# UPCNSL-ABS-FLS-POL_test-v1_0.net
KiCad netlist of a schematic drawn in Altium Designer
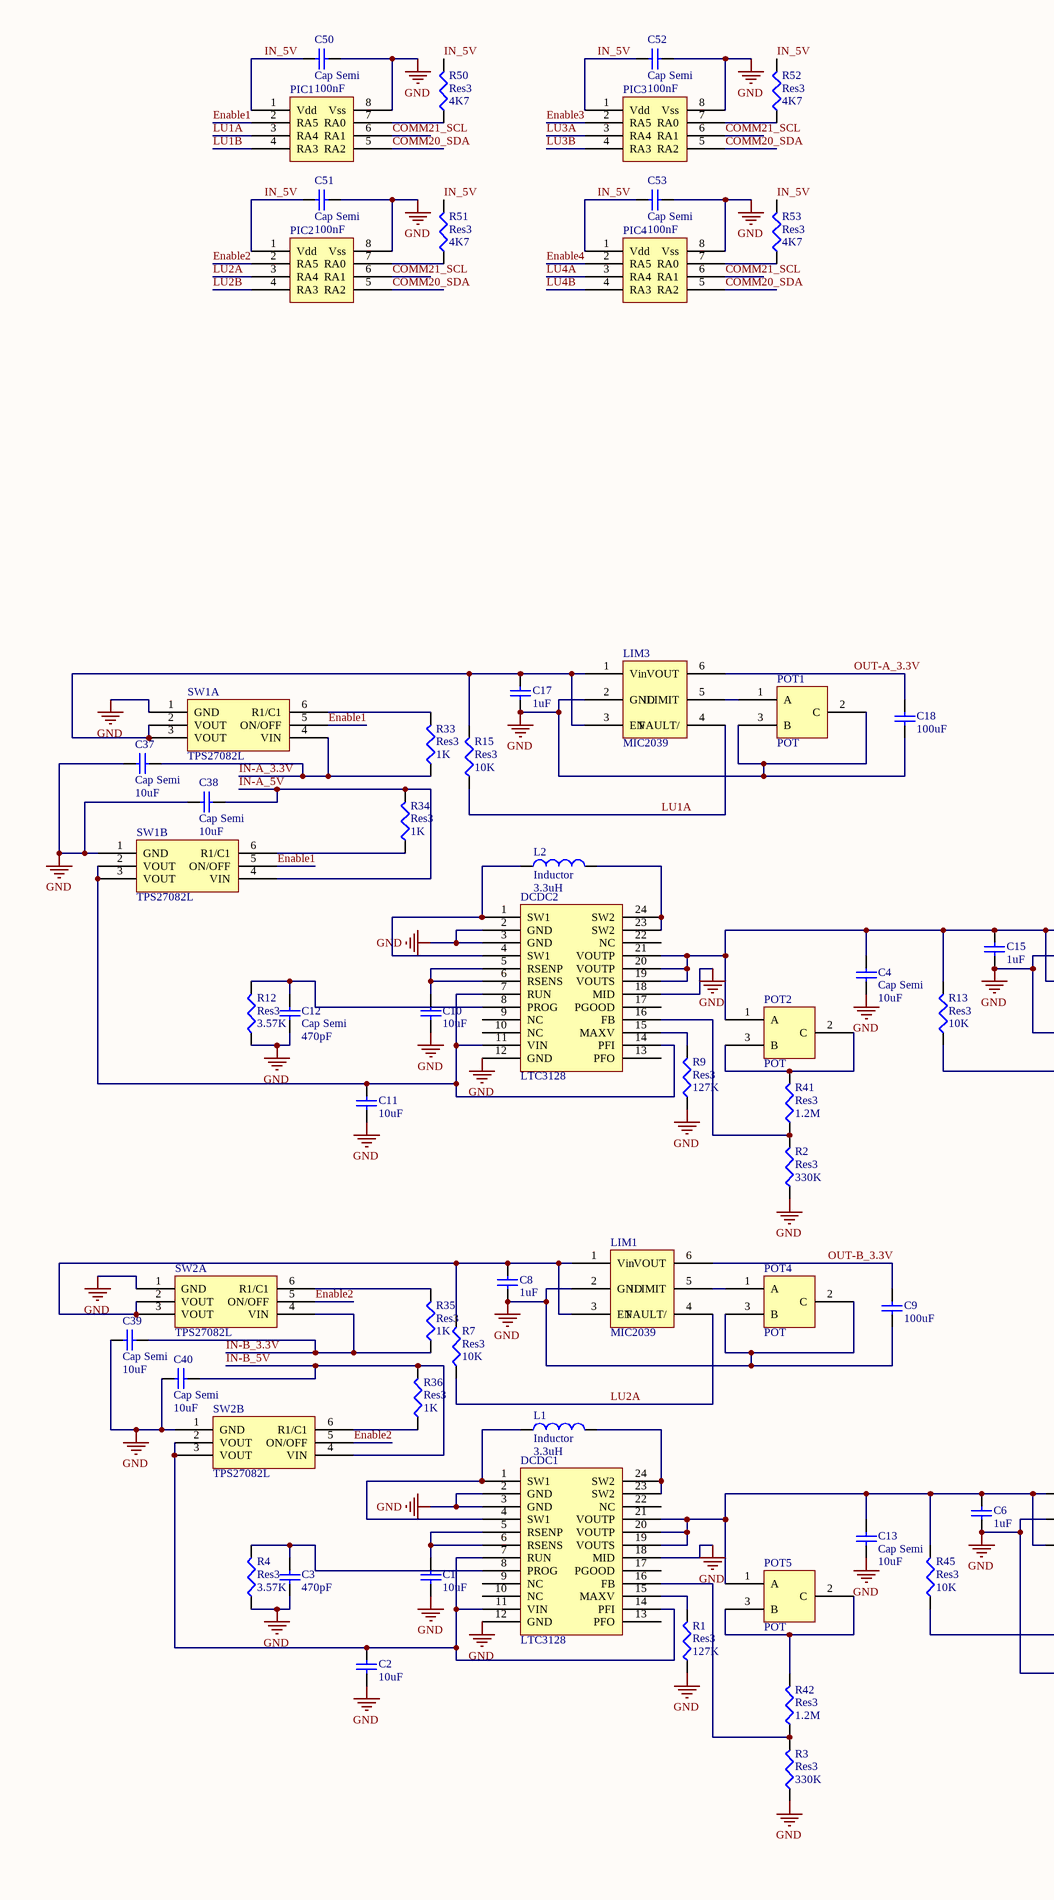
[diagram p0: UPCNSL-ABS-FLS-POL_test-v1.0.SchDoc, left]
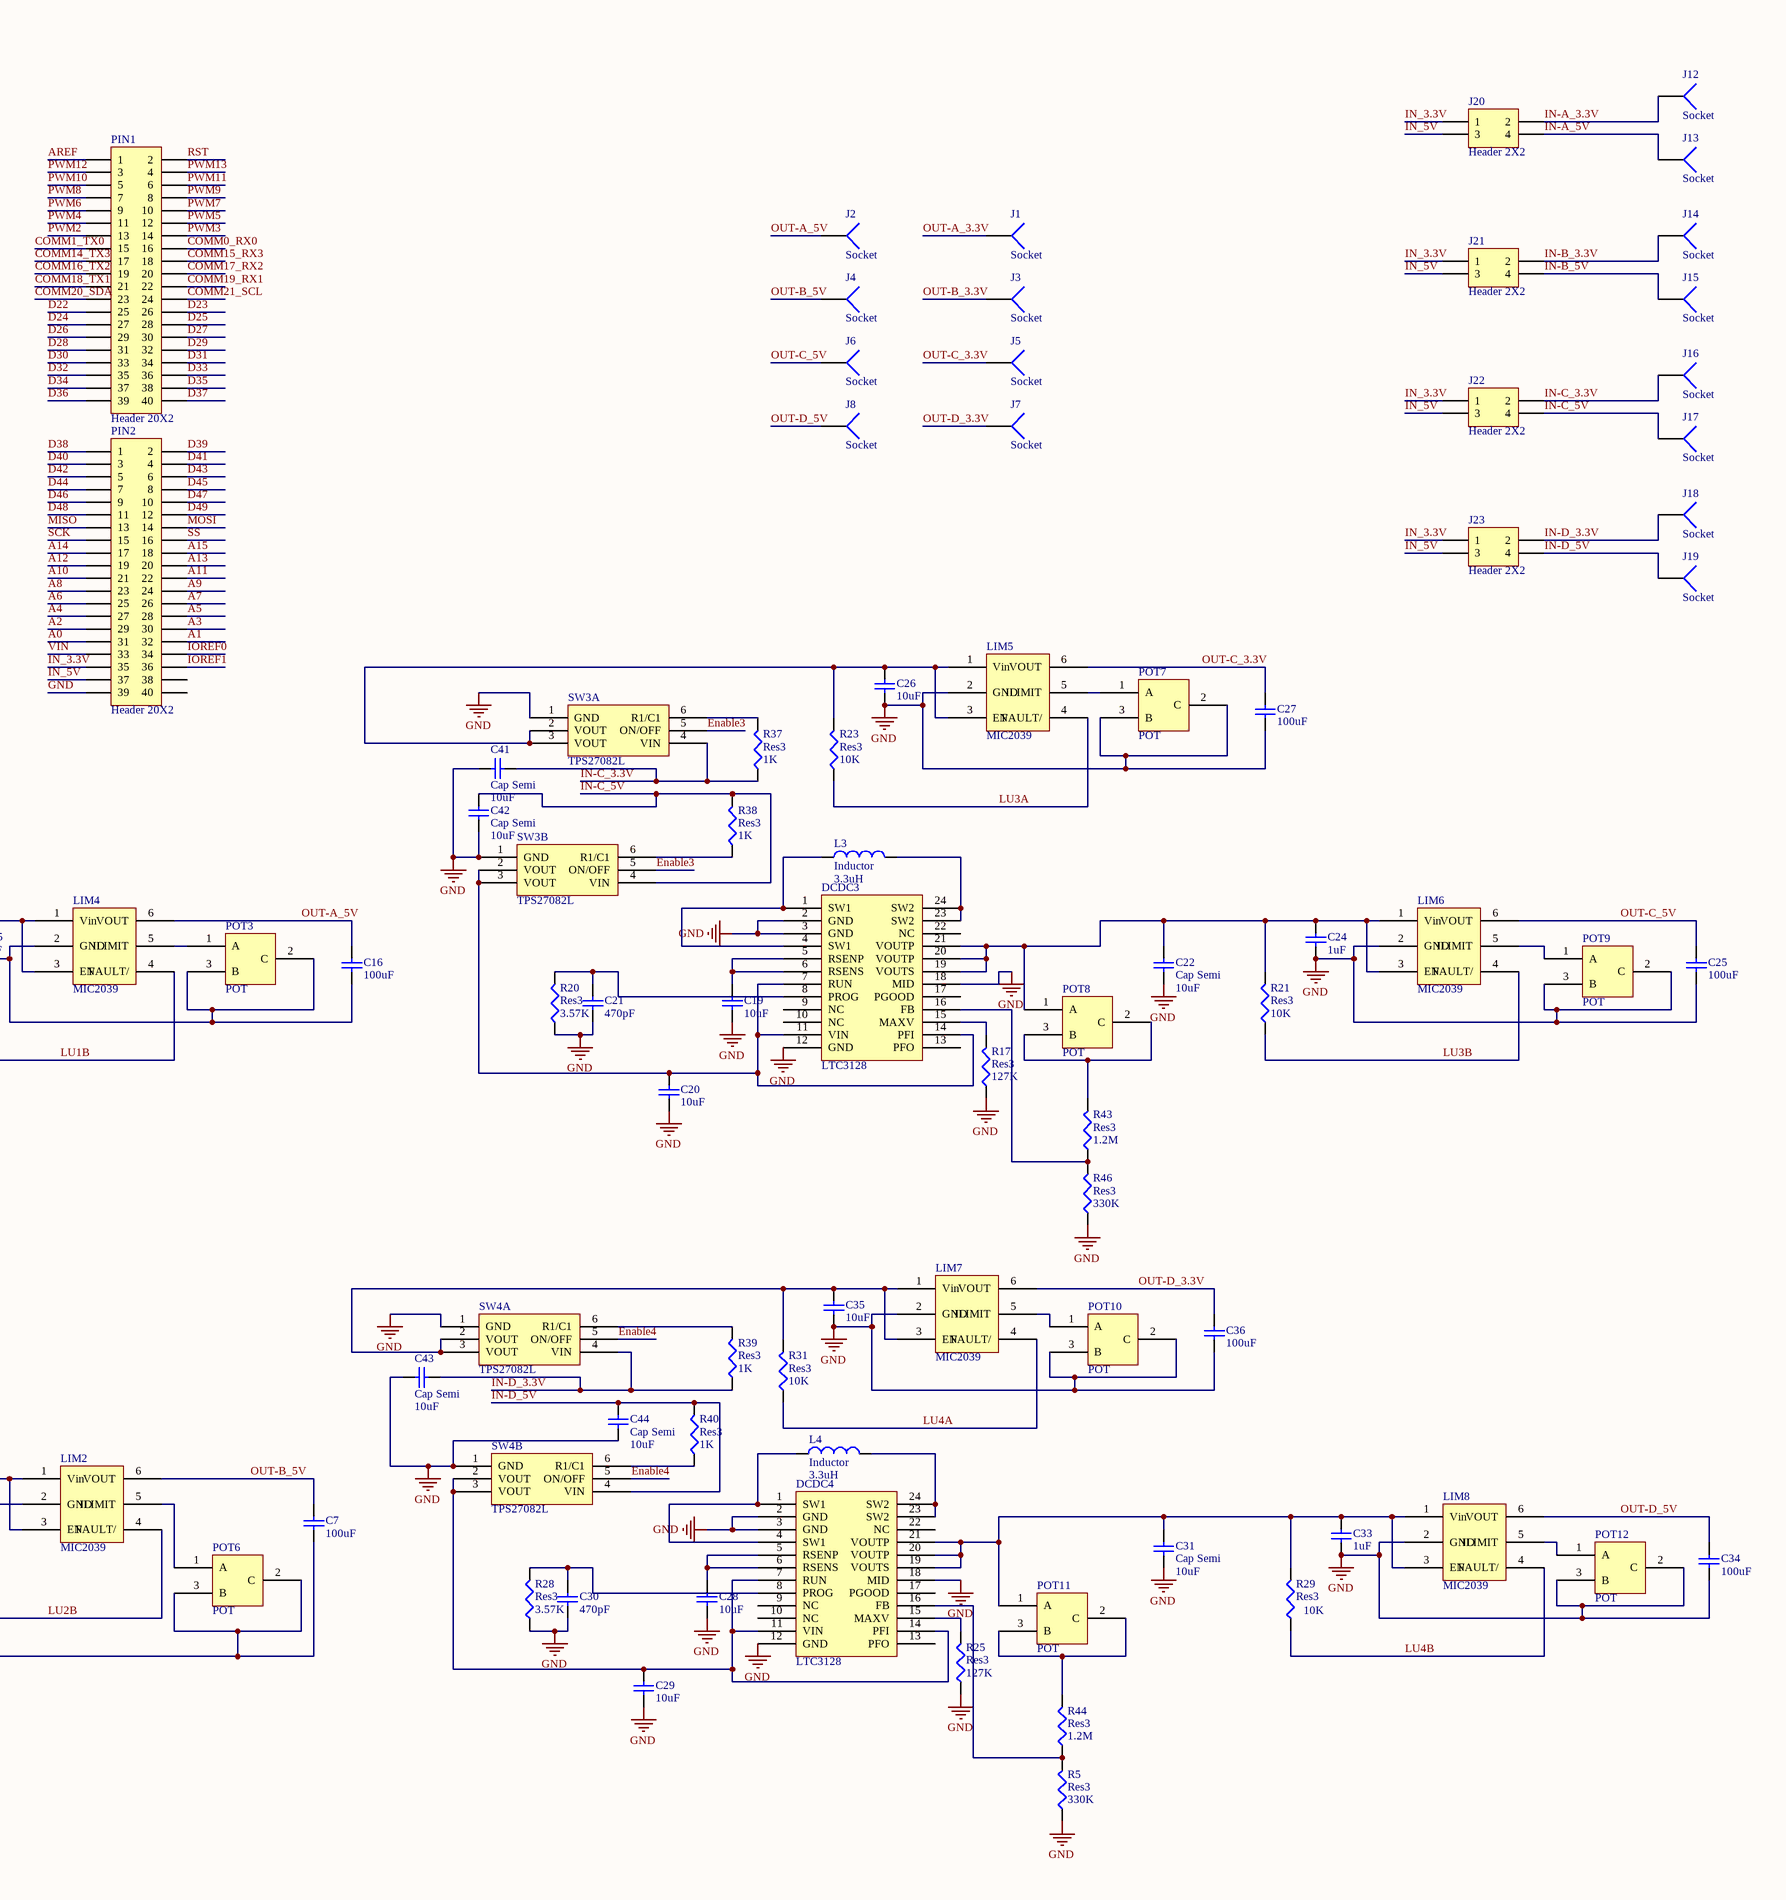
[diagram p1: UPCNSL-ABS-FLS-POL_test-v1.0.SchDoc, right]

(export (version "E")
  (design (tool "Eeschema 10.0.6"))
  (components
    (comp (ref "C1")
      (value "10uF")
      (footprint "CAP0603")
      (description "Capacitor")
      (fields (field (name "Comment") "CAP0603"))
      (libsource (lib "EPS") (part "CAP0603"))
    )
    (comp (ref "C2")
      (value "10uF")
      (footprint "CAP0603")
      (description "Capacitor")
      (fields (field (name "Comment") "CAP0603"))
      (libsource (lib "EPS") (part "CAP0603"))
    )
    (comp (ref "C3")
      (value "470pF")
      (footprint "CAP0603")
      (description "Capacitor")
      (fields (field (name "Comment") "CAP0603"))
      (libsource (lib "EPS") (part "CAP0603"))
    )
    (comp (ref "C4")
      (value "Cap Semi")
      (footprint "1608[0603]")
      (description "Capacitor (Semiconductor SIM Model)")
      (fields (field (name "ALTIUM_VALUE") "10uF") (field (name "PUBLISHER") "Altium Limited"))
      (libsource (lib "Miscellaneous Devices") (part "Cap Semi"))
    )
    (comp (ref "C6")
      (value "1uF")
      (footprint "CAP0603")
      (description "Capacitor")
      (fields (field (name "Comment") "CAP0603"))
      (libsource (lib "EPS") (part "CAP0603"))
    )
    (comp (ref "C7")
      (value "100uF")
      (footprint "CAP0603")
      (description "Capacitor")
      (fields (field (name "Comment") "CAP0603"))
      (libsource (lib "EPS") (part "CAP0603"))
    )
    (comp (ref "C8")
      (value "1uF")
      (footprint "CAP0603")
      (description "Capacitor")
      (fields (field (name "Comment") "CAP0603"))
      (libsource (lib "EPS") (part "CAP0603"))
    )
    (comp (ref "C9")
      (value "100uF")
      (footprint "CAP0603")
      (description "Capacitor")
      (fields (field (name "Comment") "CAP0603"))
      (libsource (lib "EPS") (part "CAP0603"))
    )
    (comp (ref "C10")
      (value "10uF")
      (footprint "CAP0603")
      (description "Capacitor")
      (fields (field (name "Comment") "CAP0603"))
      (libsource (lib "EPS") (part "CAP0603"))
    )
    (comp (ref "C11")
      (value "10uF")
      (footprint "CAP0603")
      (description "Capacitor")
      (fields (field (name "Comment") "CAP0603"))
      (libsource (lib "EPS") (part "CAP0603"))
    )
    (comp (ref "C12")
      (value "Cap Semi")
      (footprint "1608[0603]")
      (description "Capacitor (Semiconductor SIM Model)")
      (fields (field (name "ALTIUM_VALUE") "470pF") (field (name "PUBLISHER") "Altium Limited"))
      (libsource (lib "Miscellaneous Devices") (part "Cap Semi"))
    )
    (comp (ref "C13")
      (value "Cap Semi")
      (footprint "1608[0603]")
      (description "Capacitor (Semiconductor SIM Model)")
      (fields (field (name "ALTIUM_VALUE") "10uF") (field (name "PUBLISHER") "Altium Limited"))
      (libsource (lib "Miscellaneous Devices") (part "Cap Semi"))
    )
    (comp (ref "C15")
      (value "1uF")
      (footprint "CAP0603")
      (description "Capacitor")
      (fields (field (name "Comment") "CAP0603"))
      (libsource (lib "EPS") (part "CAP0603"))
    )
    (comp (ref "C16")
      (value "100uF")
      (footprint "CAP0603")
      (description "Capacitor")
      (fields (field (name "Comment") "CAP0603"))
      (libsource (lib "EPS") (part "CAP0603"))
    )
    (comp (ref "C17")
      (value "1uF")
      (footprint "CAP0603")
      (description "Capacitor")
      (fields (field (name "Comment") "CAP0603"))
      (libsource (lib "EPS") (part "CAP0603"))
    )
    (comp (ref "C18")
      (value "100uF")
      (footprint "CAP0603")
      (description "Capacitor")
      (fields (field (name "Comment") "CAP0603"))
      (libsource (lib "EPS") (part "CAP0603"))
    )
    (comp (ref "C19")
      (value "10uF")
      (footprint "CAP0603")
      (description "Capacitor")
      (fields (field (name "Comment") "CAP0603"))
      (libsource (lib "EPS") (part "CAP0603"))
    )
    (comp (ref "C20")
      (value "10uF")
      (footprint "CAP0603")
      (description "Capacitor")
      (fields (field (name "Comment") "CAP0603"))
      (libsource (lib "EPS") (part "CAP0603"))
    )
    (comp (ref "C21")
      (value "470pF")
      (footprint "CAP0603")
      (description "Capacitor")
      (fields (field (name "Comment") "CAP0603"))
      (libsource (lib "EPS") (part "CAP0603"))
    )
    (comp (ref "C22")
      (value "Cap Semi")
      (footprint "1608[0603]")
      (description "Capacitor (Semiconductor SIM Model)")
      (fields (field (name "ALTIUM_VALUE") "10uF") (field (name "PUBLISHER") "Altium Limited"))
      (libsource (lib "Miscellaneous Devices") (part "Cap Semi"))
    )
    (comp (ref "C24")
      (value "1uF")
      (footprint "CAP0603")
      (description "Capacitor")
      (fields (field (name "Comment") "CAP0603"))
      (libsource (lib "EPS") (part "CAP0603"))
    )
    (comp (ref "C25")
      (value "100uF")
      (footprint "CAP0603")
      (description "Capacitor")
      (fields (field (name "Comment") "CAP0603"))
      (libsource (lib "EPS") (part "CAP0603"))
    )
    (comp (ref "C26")
      (value "10uF")
      (footprint "CAP0603")
      (description "Capacitor")
      (fields (field (name "Comment") "CAP0603"))
      (libsource (lib "EPS") (part "CAP0603"))
    )
    (comp (ref "C27")
      (value "100uF")
      (footprint "CAP0603")
      (description "Capacitor")
      (fields (field (name "Comment") "CAP0603"))
      (libsource (lib "EPS") (part "CAP0603"))
    )
    (comp (ref "C28")
      (value "10uF")
      (footprint "CAP0603")
      (description "Capacitor")
      (fields (field (name "Comment") "CAP0603"))
      (libsource (lib "EPS") (part "CAP0603"))
    )
    (comp (ref "C29")
      (value "10uF")
      (footprint "CAP0603")
      (description "Capacitor")
      (fields (field (name "Comment") "CAP0603"))
      (libsource (lib "EPS") (part "CAP0603"))
    )
    (comp (ref "C30")
      (value "470pF")
      (footprint "CAP0603")
      (description "Capacitor")
      (fields (field (name "Comment") "CAP0603"))
      (libsource (lib "EPS") (part "CAP0603"))
    )
    (comp (ref "C31")
      (value "Cap Semi")
      (footprint "1608[0603]")
      (description "Capacitor (Semiconductor SIM Model)")
      (fields (field (name "ALTIUM_VALUE") "10uF") (field (name "PUBLISHER") "Altium Limited"))
      (libsource (lib "Miscellaneous Devices") (part "Cap Semi"))
    )
    (comp (ref "C33")
      (value "1uF")
      (footprint "CAP0603")
      (description "Capacitor")
      (fields (field (name "Comment") "CAP0603"))
      (libsource (lib "EPS") (part "CAP0603"))
    )
    (comp (ref "C34")
      (value "100uF")
      (footprint "CAP0603")
      (description "Capacitor")
      (fields (field (name "Comment") "CAP0603"))
      (libsource (lib "EPS") (part "CAP0603"))
    )
    (comp (ref "C35")
      (value "10uF")
      (footprint "CAP0603")
      (description "Capacitor")
      (fields (field (name "Comment") "CAP0603"))
      (libsource (lib "EPS") (part "CAP0603"))
    )
    (comp (ref "C36")
      (value "100uF")
      (footprint "CAP0603")
      (description "Capacitor")
      (fields (field (name "Comment") "CAP0603"))
      (libsource (lib "EPS") (part "CAP0603"))
    )
    (comp (ref "C37")
      (value "Cap Semi")
      (footprint "1608[0603]")
      (description "Capacitor (Semiconductor SIM Model)")
      (fields (field (name "ALTIUM_VALUE") "10uF") (field (name "PUBLISHER") "Altium Limited"))
      (libsource (lib "Miscellaneous Devices") (part "Cap Semi"))
    )
    (comp (ref "C38")
      (value "Cap Semi")
      (footprint "1608[0603]")
      (description "Capacitor (Semiconductor SIM Model)")
      (fields (field (name "ALTIUM_VALUE") "10uF") (field (name "PUBLISHER") "Altium Limited"))
      (libsource (lib "Miscellaneous Devices") (part "Cap Semi"))
    )
    (comp (ref "C39")
      (value "Cap Semi")
      (footprint "1608[0603]")
      (description "Capacitor (Semiconductor SIM Model)")
      (fields (field (name "ALTIUM_VALUE") "10uF") (field (name "PUBLISHER") "Altium Limited"))
      (libsource (lib "Miscellaneous Devices") (part "Cap Semi"))
    )
    (comp (ref "C40")
      (value "Cap Semi")
      (footprint "1608[0603]")
      (description "Capacitor (Semiconductor SIM Model)")
      (fields (field (name "ALTIUM_VALUE") "10uF") (field (name "PUBLISHER") "Altium Limited"))
      (libsource (lib "Miscellaneous Devices") (part "Cap Semi"))
    )
    (comp (ref "C41")
      (value "Cap Semi")
      (footprint "1608[0603]")
      (description "Capacitor (Semiconductor SIM Model)")
      (fields (field (name "ALTIUM_VALUE") "10uF") (field (name "PUBLISHER") "Altium Limited"))
      (libsource (lib "Miscellaneous Devices") (part "Cap Semi"))
    )
    (comp (ref "C42")
      (value "Cap Semi")
      (footprint "1608[0603]")
      (description "Capacitor (Semiconductor SIM Model)")
      (fields (field (name "ALTIUM_VALUE") "10uF") (field (name "PUBLISHER") "Altium Limited"))
      (libsource (lib "Miscellaneous Devices") (part "Cap Semi"))
    )
    (comp (ref "C43")
      (value "Cap Semi")
      (footprint "1608[0603]")
      (description "Capacitor (Semiconductor SIM Model)")
      (fields (field (name "ALTIUM_VALUE") "10uF") (field (name "PUBLISHER") "Altium Limited"))
      (libsource (lib "Miscellaneous Devices") (part "Cap Semi"))
    )
    (comp (ref "C44")
      (value "Cap Semi")
      (footprint "1608[0603]")
      (description "Capacitor (Semiconductor SIM Model)")
      (fields (field (name "ALTIUM_VALUE") "10uF") (field (name "PUBLISHER") "Altium Limited"))
      (libsource (lib "Miscellaneous Devices") (part "Cap Semi"))
    )
    (comp (ref "C50")
      (value "Cap Semi")
      (footprint "1608[0603]")
      (description "Capacitor (Semiconductor SIM Model)")
      (fields (field (name "ALTIUM_VALUE") "100nF") (field (name "PUBLISHER") "Altium Limited"))
      (libsource (lib "Miscellaneous Devices") (part "Cap Semi"))
    )
    (comp (ref "C51")
      (value "Cap Semi")
      (footprint "1608[0603]")
      (description "Capacitor (Semiconductor SIM Model)")
      (fields (field (name "ALTIUM_VALUE") "100nF") (field (name "PUBLISHER") "Altium Limited"))
      (libsource (lib "Miscellaneous Devices") (part "Cap Semi"))
    )
    (comp (ref "C52")
      (value "Cap Semi")
      (footprint "1608[0603]")
      (description "Capacitor (Semiconductor SIM Model)")
      (fields (field (name "ALTIUM_VALUE") "100nF") (field (name "PUBLISHER") "Altium Limited"))
      (libsource (lib "Miscellaneous Devices") (part "Cap Semi"))
    )
    (comp (ref "C53")
      (value "Cap Semi")
      (footprint "1608[0603]")
      (description "Capacitor (Semiconductor SIM Model)")
      (fields (field (name "ALTIUM_VALUE") "100nF") (field (name "PUBLISHER") "Altium Limited"))
      (libsource (lib "Miscellaneous Devices") (part "Cap Semi"))
    )
    (comp (ref "DCDC1")
      (value "LTC3128")
      (footprint "SOP-24")
      (libsource (lib "FLATSAT_PHONE_DCDC2") (part "Component_1"))
    )
    (comp (ref "DCDC2")
      (value "LTC3128")
      (footprint "SOP-24")
      (libsource (lib "FLATSAT_PHONE_DCDC2") (part "Component_1"))
    )
    (comp (ref "DCDC3")
      (value "LTC3128")
      (footprint "SOP-24")
      (libsource (lib "FLATSAT_PHONE_DCDC2") (part "Component_1"))
    )
    (comp (ref "DCDC4")
      (value "LTC3128")
      (footprint "SOP-24")
      (libsource (lib "FLATSAT_PHONE_DCDC2") (part "Component_1"))
    )
    (comp (ref "J1")
      (value "Socket")
      (footprint "PIN1")
      (fields (field (name "PUBLISHER") "Altium Limited"))
      (libsource (lib "Miscellaneous Connectors") (part "Socket"))
    )
    (comp (ref "J2")
      (value "Socket")
      (footprint "PIN1")
      (fields (field (name "PUBLISHER") "Altium Limited"))
      (libsource (lib "Miscellaneous Connectors") (part "Socket"))
    )
    (comp (ref "J3")
      (value "Socket")
      (footprint "PIN1")
      (fields (field (name "PUBLISHER") "Altium Limited"))
      (libsource (lib "Miscellaneous Connectors") (part "Socket"))
    )
    (comp (ref "J4")
      (value "Socket")
      (footprint "PIN1")
      (fields (field (name "PUBLISHER") "Altium Limited"))
      (libsource (lib "Miscellaneous Connectors") (part "Socket"))
    )
    (comp (ref "J5")
      (value "Socket")
      (footprint "PIN1")
      (fields (field (name "PUBLISHER") "Altium Limited"))
      (libsource (lib "Miscellaneous Connectors") (part "Socket"))
    )
    (comp (ref "J6")
      (value "Socket")
      (footprint "PIN1")
      (fields (field (name "PUBLISHER") "Altium Limited"))
      (libsource (lib "Miscellaneous Connectors") (part "Socket"))
    )
    (comp (ref "J7")
      (value "Socket")
      (footprint "PIN1")
      (fields (field (name "PUBLISHER") "Altium Limited"))
      (libsource (lib "Miscellaneous Connectors") (part "Socket"))
    )
    (comp (ref "J8")
      (value "Socket")
      (footprint "PIN1")
      (fields (field (name "PUBLISHER") "Altium Limited"))
      (libsource (lib "Miscellaneous Connectors") (part "Socket"))
    )
    (comp (ref "J12")
      (value "Socket")
      (footprint "PIN1")
      (fields (field (name "PUBLISHER") "Altium Limited"))
      (libsource (lib "Miscellaneous Connectors") (part "Socket"))
    )
    (comp (ref "J13")
      (value "Socket")
      (footprint "PIN1")
      (fields (field (name "PUBLISHER") "Altium Limited"))
      (libsource (lib "Miscellaneous Connectors") (part "Socket"))
    )
    (comp (ref "J14")
      (value "Socket")
      (footprint "PIN1")
      (fields (field (name "PUBLISHER") "Altium Limited"))
      (libsource (lib "Miscellaneous Connectors") (part "Socket"))
    )
    (comp (ref "J15")
      (value "Socket")
      (footprint "PIN1")
      (fields (field (name "PUBLISHER") "Altium Limited"))
      (libsource (lib "Miscellaneous Connectors") (part "Socket"))
    )
    (comp (ref "J16")
      (value "Socket")
      (footprint "PIN1")
      (fields (field (name "PUBLISHER") "Altium Limited"))
      (libsource (lib "Miscellaneous Connectors") (part "Socket"))
    )
    (comp (ref "J17")
      (value "Socket")
      (footprint "PIN1")
      (fields (field (name "PUBLISHER") "Altium Limited"))
      (libsource (lib "Miscellaneous Connectors") (part "Socket"))
    )
    (comp (ref "J18")
      (value "Socket")
      (footprint "PIN1")
      (fields (field (name "PUBLISHER") "Altium Limited"))
      (libsource (lib "Miscellaneous Connectors") (part "Socket"))
    )
    (comp (ref "J19")
      (value "Socket")
      (footprint "PIN1")
      (fields (field (name "PUBLISHER") "Altium Limited"))
      (libsource (lib "Miscellaneous Connectors") (part "Socket"))
    )
    (comp (ref "J20")
      (value "Header 2X2")
      (footprint "HDR2X2")
      (description "Header, 2-Pin, Dual row")
      (fields (field (name "PUBLISHER") "Altium Limited"))
      (libsource (lib "Miscellaneous Connectors") (part "Header 2X2"))
    )
    (comp (ref "J21")
      (value "Header 2X2")
      (footprint "HDR2X2")
      (description "Header, 2-Pin, Dual row")
      (fields (field (name "PUBLISHER") "Altium Limited"))
      (libsource (lib "Miscellaneous Connectors") (part "Header 2X2"))
    )
    (comp (ref "J22")
      (value "Header 2X2")
      (footprint "HDR2X2")
      (description "Header, 2-Pin, Dual row")
      (fields (field (name "PUBLISHER") "Altium Limited"))
      (libsource (lib "Miscellaneous Connectors") (part "Header 2X2"))
    )
    (comp (ref "J23")
      (value "Header 2X2")
      (footprint "HDR2X2")
      (description "Header, 2-Pin, Dual row")
      (fields (field (name "PUBLISHER") "Altium Limited"))
      (libsource (lib "Miscellaneous Connectors") (part "Header 2X2"))
    )
    (comp (ref "L1")
      (value "Inductor")
      (footprint "MPLC0703R3")
      (fields (field (name "ALTIUM_VALUE") "3.3uH") (field (name "PUBLISHER") "Altium Limited"))
      (libsource (lib "Miscellaneous Devices") (part "Inductor"))
    )
    (comp (ref "L2")
      (value "Inductor")
      (footprint "MPLC0703R3")
      (fields (field (name "ALTIUM_VALUE") "3.3uH") (field (name "PUBLISHER") "Altium Limited"))
      (libsource (lib "Miscellaneous Devices") (part "Inductor"))
    )
    (comp (ref "L3")
      (value "Inductor")
      (footprint "MPLC0703R3")
      (fields (field (name "ALTIUM_VALUE") "3.3uH") (field (name "PUBLISHER") "Altium Limited"))
      (libsource (lib "Miscellaneous Devices") (part "Inductor"))
    )
    (comp (ref "L4")
      (value "Inductor")
      (footprint "MPLC0703R3")
      (fields (field (name "ALTIUM_VALUE") "3.3uH") (field (name "PUBLISHER") "Altium Limited"))
      (libsource (lib "Miscellaneous Devices") (part "Inductor"))
    )
    (comp (ref "LIM1")
      (value "MIC2039")
      (footprint "SOT23-6_M")
      (libsource (lib "FLATSAT_PHONE") (part "MIC2039"))
    )
    (comp (ref "LIM2")
      (value "MIC2039")
      (footprint "SOT23-6_M")
      (libsource (lib "FLATSAT_PHONE") (part "MIC2039"))
    )
    (comp (ref "LIM3")
      (value "MIC2039")
      (footprint "SOT23-6_M")
      (libsource (lib "FLATSAT_PHONE") (part "MIC2039"))
    )
    (comp (ref "LIM4")
      (value "MIC2039")
      (footprint "SOT23-6_M")
      (libsource (lib "FLATSAT_PHONE") (part "MIC2039"))
    )
    (comp (ref "LIM5")
      (value "MIC2039")
      (footprint "SOT23-6_M")
      (libsource (lib "FLATSAT_PHONE") (part "MIC2039"))
    )
    (comp (ref "LIM6")
      (value "MIC2039")
      (footprint "SOT23-6_M")
      (libsource (lib "FLATSAT_PHONE") (part "MIC2039"))
    )
    (comp (ref "LIM7")
      (value "MIC2039")
      (footprint "SOT23-6_M")
      (libsource (lib "FLATSAT_PHONE") (part "MIC2039"))
    )
    (comp (ref "LIM8")
      (value "MIC2039")
      (footprint "SOT23-6_M")
      (libsource (lib "FLATSAT_PHONE") (part "MIC2039"))
    )
    (comp (ref "PIC1")
      (value "SOCOL-8P")
      (footprint "SOCOL-8P")
      (libsource (lib "SOCOL-8P") (part "SOCOL-8P"))
    )
    (comp (ref "PIC2")
      (value "SOCOL-8P")
      (footprint "SOCOL-8P")
      (libsource (lib "SOCOL-8P") (part "SOCOL-8P"))
    )
    (comp (ref "PIC3")
      (value "SOCOL-8P")
      (footprint "SOCOL-8P")
      (libsource (lib "SOCOL-8P") (part "SOCOL-8P"))
    )
    (comp (ref "PIC4")
      (value "SOCOL-8P")
      (footprint "SOCOL-8P")
      (libsource (lib "SOCOL-8P") (part "SOCOL-8P"))
    )
    (comp (ref "PIN1")
      (value "Header 20X2")
      (footprint "HDR2X20")
      (description "Header, 20-Pin, Dual row")
      (fields (field (name "PUBLISHER") "Altium Limited"))
      (libsource (lib "Miscellaneous Connectors") (part "Header 20X2"))
    )
    (comp (ref "PIN2")
      (value "Header 20X2")
      (footprint "HDR2X20")
      (description "Header, 20-Pin, Dual row")
      (fields (field (name "PUBLISHER") "Altium Limited"))
      (libsource (lib "Miscellaneous Connectors") (part "Header 20X2"))
    )
    (comp (ref "POT1")
      (value "POT")
      (footprint "POT")
      (libsource (lib "FLATSAT_PHONE_POT") (part "component_1"))
    )
    (comp (ref "POT2")
      (value "POT")
      (footprint "POT2")
      (libsource (lib "FLATSAT_PHONE_POT") (part "component_1"))
    )
    (comp (ref "POT3")
      (value "POT")
      (footprint "POT")
      (libsource (lib "FLATSAT_PHONE_POT") (part "component_1"))
    )
    (comp (ref "POT4")
      (value "POT")
      (footprint "POT")
      (libsource (lib "FLATSAT_PHONE_POT") (part "component_1"))
    )
    (comp (ref "POT5")
      (value "POT")
      (footprint "POT2")
      (libsource (lib "FLATSAT_PHONE_POT") (part "component_1"))
    )
    (comp (ref "POT6")
      (value "POT")
      (footprint "POT")
      (libsource (lib "FLATSAT_PHONE_POT") (part "component_1"))
    )
    (comp (ref "POT7")
      (value "POT")
      (footprint "POT")
      (libsource (lib "FLATSAT_PHONE_POT") (part "component_1"))
    )
    (comp (ref "POT8")
      (value "POT")
      (footprint "POT2")
      (libsource (lib "FLATSAT_PHONE_POT") (part "component_1"))
    )
    (comp (ref "POT9")
      (value "POT")
      (footprint "POT")
      (libsource (lib "FLATSAT_PHONE_POT") (part "component_1"))
    )
    (comp (ref "POT10")
      (value "POT")
      (footprint "POT")
      (libsource (lib "FLATSAT_PHONE_POT") (part "component_1"))
    )
    (comp (ref "POT11")
      (value "POT")
      (footprint "POT2")
      (libsource (lib "FLATSAT_PHONE_POT") (part "component_1"))
    )
    (comp (ref "POT12")
      (value "POT")
      (footprint "POT")
      (libsource (lib "FLATSAT_PHONE_POT") (part "component_1"))
    )
    (comp (ref "R1")
      (value "Res3")
      (footprint "J1-0603")
      (description "Resistor")
      (fields (field (name "ALTIUM_VALUE") "127K") (field (name "PUBLISHER") "Altium Limited"))
      (libsource (lib "Miscellaneous Devices") (part "Res3"))
    )
    (comp (ref "R2")
      (value "Res3")
      (footprint "J1-0603")
      (description "Resistor")
      (fields (field (name "ALTIUM_VALUE") "330K") (field (name "PUBLISHER") "Altium Limited"))
      (libsource (lib "Miscellaneous Devices") (part "Res3"))
    )
    (comp (ref "R3")
      (value "Res3")
      (footprint "J1-0603")
      (description "Resistor")
      (fields (field (name "ALTIUM_VALUE") "330K") (field (name "PUBLISHER") "Altium Limited"))
      (libsource (lib "Miscellaneous Devices") (part "Res3"))
    )
    (comp (ref "R4")
      (value "Res3")
      (footprint "J1-0603")
      (description "Resistor")
      (fields (field (name "ALTIUM_VALUE") "3.57K") (field (name "PUBLISHER") "Altium Limited"))
      (libsource (lib "Miscellaneous Devices") (part "Res3"))
    )
    (comp (ref "R5")
      (value "Res3")
      (footprint "J1-0603")
      (description "Resistor")
      (fields (field (name "ALTIUM_VALUE") "330K") (field (name "PUBLISHER") "Altium Limited"))
      (libsource (lib "Miscellaneous Devices") (part "Res3"))
    )
    (comp (ref "R7")
      (value "Res3")
      (footprint "J1-0603")
      (description "Resistor")
      (fields (field (name "ALTIUM_VALUE") "10K") (field (name "PUBLISHER") "Altium Limited"))
      (libsource (lib "Miscellaneous Devices") (part "Res3"))
    )
    (comp (ref "R9")
      (value "Res3")
      (footprint "J1-0603")
      (description "Resistor")
      (fields (field (name "ALTIUM_VALUE") "127K") (field (name "PUBLISHER") "Altium Limited"))
      (libsource (lib "Miscellaneous Devices") (part "Res3"))
    )
    (comp (ref "R12")
      (value "Res3")
      (footprint "J1-0603")
      (description "Resistor")
      (fields (field (name "ALTIUM_VALUE") "3.57K") (field (name "PUBLISHER") "Altium Limited"))
      (libsource (lib "Miscellaneous Devices") (part "Res3"))
    )
    (comp (ref "R13")
      (value "Res3")
      (footprint "J1-0603")
      (description "Resistor")
      (fields (field (name "ALTIUM_VALUE") "10K") (field (name "PUBLISHER") "Altium Limited"))
      (libsource (lib "Miscellaneous Devices") (part "Res3"))
    )
    (comp (ref "R15")
      (value "Res3")
      (footprint "J1-0603")
      (description "Resistor")
      (fields (field (name "ALTIUM_VALUE") "10K") (field (name "PUBLISHER") "Altium Limited"))
      (libsource (lib "Miscellaneous Devices") (part "Res3"))
    )
    (comp (ref "R17")
      (value "Res3")
      (footprint "J1-0603")
      (description "Resistor")
      (fields (field (name "ALTIUM_VALUE") "127K") (field (name "PUBLISHER") "Altium Limited"))
      (libsource (lib "Miscellaneous Devices") (part "Res3"))
    )
    (comp (ref "R20")
      (value "Res3")
      (footprint "J1-0603")
      (description "Resistor")
      (fields (field (name "ALTIUM_VALUE") "3.57K") (field (name "PUBLISHER") "Altium Limited"))
      (libsource (lib "Miscellaneous Devices") (part "Res3"))
    )
    (comp (ref "R21")
      (value "Res3")
      (footprint "J1-0603")
      (description "Resistor")
      (fields (field (name "ALTIUM_VALUE") "10K") (field (name "PUBLISHER") "Altium Limited"))
      (libsource (lib "Miscellaneous Devices") (part "Res3"))
    )
    (comp (ref "R23")
      (value "Res3")
      (footprint "J1-0603")
      (description "Resistor")
      (fields (field (name "ALTIUM_VALUE") "10K") (field (name "PUBLISHER") "Altium Limited"))
      (libsource (lib "Miscellaneous Devices") (part "Res3"))
    )
    (comp (ref "R25")
      (value "Res3")
      (footprint "J1-0603")
      (description "Resistor")
      (fields (field (name "ALTIUM_VALUE") "127K") (field (name "PUBLISHER") "Altium Limited"))
      (libsource (lib "Miscellaneous Devices") (part "Res3"))
    )
    (comp (ref "R28")
      (value "Res3")
      (footprint "J1-0603")
      (description "Resistor")
      (fields (field (name "ALTIUM_VALUE") "3.57K") (field (name "PUBLISHER") "Altium Limited"))
      (libsource (lib "Miscellaneous Devices") (part "Res3"))
    )
    (comp (ref "R29")
      (value "Res3")
      (footprint "J1-0603")
      (description "Resistor")
      (fields (field (name "ALTIUM_VALUE") "10K") (field (name "PUBLISHER") "Altium Limited"))
      (libsource (lib "Miscellaneous Devices") (part "Res3"))
    )
    (comp (ref "R31")
      (value "Res3")
      (footprint "J1-0603")
      (description "Resistor")
      (fields (field (name "ALTIUM_VALUE") "10K") (field (name "PUBLISHER") "Altium Limited"))
      (libsource (lib "Miscellaneous Devices") (part "Res3"))
    )
    (comp (ref "R33")
      (value "Res3")
      (footprint "J1-0603")
      (description "Resistor")
      (fields (field (name "ALTIUM_VALUE") "1K") (field (name "PUBLISHER") "Altium Limited"))
      (libsource (lib "Miscellaneous Devices") (part "Res3"))
    )
    (comp (ref "R34")
      (value "Res3")
      (footprint "J1-0603")
      (description "Resistor")
      (fields (field (name "ALTIUM_VALUE") "1K") (field (name "PUBLISHER") "Altium Limited"))
      (libsource (lib "Miscellaneous Devices") (part "Res3"))
    )
    (comp (ref "R35")
      (value "Res3")
      (footprint "J1-0603")
      (description "Resistor")
      (fields (field (name "ALTIUM_VALUE") "1K") (field (name "PUBLISHER") "Altium Limited"))
      (libsource (lib "Miscellaneous Devices") (part "Res3"))
    )
    (comp (ref "R36")
      (value "Res3")
      (footprint "J1-0603")
      (description "Resistor")
      (fields (field (name "ALTIUM_VALUE") "1K") (field (name "PUBLISHER") "Altium Limited"))
      (libsource (lib "Miscellaneous Devices") (part "Res3"))
    )
    (comp (ref "R37")
      (value "Res3")
      (footprint "J1-0603")
      (description "Resistor")
      (fields (field (name "ALTIUM_VALUE") "1K") (field (name "PUBLISHER") "Altium Limited"))
      (libsource (lib "Miscellaneous Devices") (part "Res3"))
    )
    (comp (ref "R38")
      (value "Res3")
      (footprint "J1-0603")
      (description "Resistor")
      (fields (field (name "ALTIUM_VALUE") "1K") (field (name "PUBLISHER") "Altium Limited"))
      (libsource (lib "Miscellaneous Devices") (part "Res3"))
    )
    (comp (ref "R39")
      (value "Res3")
      (footprint "J1-0603")
      (description "Resistor")
      (fields (field (name "ALTIUM_VALUE") "1K") (field (name "PUBLISHER") "Altium Limited"))
      (libsource (lib "Miscellaneous Devices") (part "Res3"))
    )
    (comp (ref "R40")
      (value "Res3")
      (footprint "J1-0603")
      (description "Resistor")
      (fields (field (name "ALTIUM_VALUE") "1K") (field (name "PUBLISHER") "Altium Limited"))
      (libsource (lib "Miscellaneous Devices") (part "Res3"))
    )
    (comp (ref "R41")
      (value "Res3")
      (footprint "J1-0603")
      (description "Resistor")
      (fields (field (name "ALTIUM_VALUE") "1.2M") (field (name "PUBLISHER") "Altium Limited"))
      (libsource (lib "Miscellaneous Devices") (part "Res3"))
    )
    (comp (ref "R42")
      (value "Res3")
      (footprint "J1-0603")
      (description "Resistor")
      (fields (field (name "ALTIUM_VALUE") "1.2M") (field (name "PUBLISHER") "Altium Limited"))
      (libsource (lib "Miscellaneous Devices") (part "Res3"))
    )
    (comp (ref "R43")
      (value "Res3")
      (footprint "J1-0603")
      (description "Resistor")
      (fields (field (name "ALTIUM_VALUE") "1.2M") (field (name "PUBLISHER") "Altium Limited"))
      (libsource (lib "Miscellaneous Devices") (part "Res3"))
    )
    (comp (ref "R44")
      (value "Res3")
      (footprint "J1-0603")
      (description "Resistor")
      (fields (field (name "ALTIUM_VALUE") "1.2M") (field (name "PUBLISHER") "Altium Limited"))
      (libsource (lib "Miscellaneous Devices") (part "Res3"))
    )
    (comp (ref "R45")
      (value "Res3")
      (footprint "J1-0603")
      (description "Resistor")
      (fields (field (name "ALTIUM_VALUE") "10K") (field (name "PUBLISHER") "Altium Limited"))
      (libsource (lib "Miscellaneous Devices") (part "Res3"))
    )
    (comp (ref "R46")
      (value "Res3")
      (footprint "J1-0603")
      (description "Resistor")
      (fields (field (name "ALTIUM_VALUE") "330K") (field (name "PUBLISHER") "Altium Limited"))
      (libsource (lib "Miscellaneous Devices") (part "Res3"))
    )
    (comp (ref "R50")
      (value "Res3")
      (footprint "J1-0603")
      (description "Resistor")
      (fields (field (name "ALTIUM_VALUE") "4K7") (field (name "PUBLISHER") "Altium Limited"))
      (libsource (lib "Miscellaneous Devices") (part "Res3"))
    )
    (comp (ref "R51")
      (value "Res3")
      (footprint "J1-0603")
      (description "Resistor")
      (fields (field (name "ALTIUM_VALUE") "4K7") (field (name "PUBLISHER") "Altium Limited"))
      (libsource (lib "Miscellaneous Devices") (part "Res3"))
    )
    (comp (ref "R52")
      (value "Res3")
      (footprint "J1-0603")
      (description "Resistor")
      (fields (field (name "ALTIUM_VALUE") "4K7") (field (name "PUBLISHER") "Altium Limited"))
      (libsource (lib "Miscellaneous Devices") (part "Res3"))
    )
    (comp (ref "R53")
      (value "Res3")
      (footprint "J1-0603")
      (description "Resistor")
      (fields (field (name "ALTIUM_VALUE") "4K7") (field (name "PUBLISHER") "Altium Limited"))
      (libsource (lib "Miscellaneous Devices") (part "Res3"))
    )
    (comp (ref "SW1A")
      (value "TPS27082L")
      (footprint "TPS27081A")
      (libsource (lib "TPS27082L") (part "TPS27082L"))
    )
    (comp (ref "SW1B")
      (value "TPS27082L")
      (footprint "TPS27081A")
      (libsource (lib "TPS27082L") (part "TPS27082L"))
    )
    (comp (ref "SW2A")
      (value "TPS27082L")
      (footprint "TPS27081A")
      (libsource (lib "TPS27082L") (part "TPS27082L"))
    )
    (comp (ref "SW2B")
      (value "TPS27082L")
      (footprint "TPS27081A")
      (libsource (lib "TPS27082L") (part "TPS27082L"))
    )
    (comp (ref "SW3A")
      (value "TPS27082L")
      (footprint "TPS27081A")
      (libsource (lib "TPS27082L") (part "TPS27082L"))
    )
    (comp (ref "SW3B")
      (value "TPS27082L")
      (footprint "TPS27081A")
      (libsource (lib "TPS27082L") (part "TPS27082L"))
    )
    (comp (ref "SW4A")
      (value "TPS27082L")
      (footprint "TPS27081A")
      (libsource (lib "TPS27082L") (part "TPS27082L"))
    )
    (comp (ref "SW4B")
      (value "TPS27082L")
      (footprint "TPS27081A")
      (libsource (lib "TPS27082L") (part "TPS27082L"))
    )
  )
  (nets
    (net (code "1") (name "/A0") (class "Default")
      (node (ref "PIN2") (pin "31") (pinfunction "31_31") (pintype "passive"))
    )
    (net (code "2") (name "/A1") (class "Default")
      (node (ref "PIN2") (pin "32") (pinfunction "32_32") (pintype "passive"))
    )
    (net (code "3") (name "/A2") (class "Default")
      (node (ref "PIN2") (pin "29") (pinfunction "29_29") (pintype "passive"))
    )
    (net (code "4") (name "/A3") (class "Default")
      (node (ref "PIN2") (pin "30") (pinfunction "30_30") (pintype "passive"))
    )
    (net (code "5") (name "/A4") (class "Default")
      (node (ref "PIN2") (pin "27") (pinfunction "27_27") (pintype "passive"))
    )
    (net (code "6") (name "/A5") (class "Default")
      (node (ref "PIN2") (pin "28") (pinfunction "28_28") (pintype "passive"))
    )
    (net (code "7") (name "/A6") (class "Default")
      (node (ref "PIN2") (pin "25") (pinfunction "25_25") (pintype "passive"))
    )
    (net (code "8") (name "/A7") (class "Default")
      (node (ref "PIN2") (pin "26") (pinfunction "26_26") (pintype "passive"))
    )
    (net (code "9") (name "/A8") (class "Default")
      (node (ref "PIN2") (pin "23") (pinfunction "23_23") (pintype "passive"))
    )
    (net (code "10") (name "/A9") (class "Default")
      (node (ref "PIN2") (pin "24") (pinfunction "24_24") (pintype "passive"))
    )
    (net (code "11") (name "/A10") (class "Default")
      (node (ref "PIN2") (pin "21") (pinfunction "21_21") (pintype "passive"))
    )
    (net (code "12") (name "/A11") (class "Default")
      (node (ref "PIN2") (pin "22") (pinfunction "22_22") (pintype "passive"))
    )
    (net (code "13") (name "/A12") (class "Default")
      (node (ref "PIN2") (pin "19") (pinfunction "19_19") (pintype "passive"))
    )
    (net (code "14") (name "/A13") (class "Default")
      (node (ref "PIN2") (pin "20") (pinfunction "20_20") (pintype "passive"))
    )
    (net (code "15") (name "/A14") (class "Default")
      (node (ref "PIN2") (pin "17") (pinfunction "17_17") (pintype "passive"))
    )
    (net (code "16") (name "/A15") (class "Default")
      (node (ref "PIN2") (pin "18") (pinfunction "18_18") (pintype "passive"))
    )
    (net (code "17") (name "/AREF") (class "Default")
      (node (ref "PIN1") (pin "1") (pinfunction "1_1") (pintype "passive"))
    )
    (net (code "18") (name "/COMM0_RX0") (class "Default")
      (node (ref "PIN1") (pin "16") (pinfunction "16_16") (pintype "passive"))
    )
    (net (code "19") (name "/COMM1_TX0") (class "Default")
      (node (ref "PIN1") (pin "15") (pinfunction "15_15") (pintype "passive"))
    )
    (net (code "20") (name "/COMM14_TX3") (class "Default")
      (node (ref "PIN1") (pin "17") (pinfunction "17_17") (pintype "passive"))
    )
    (net (code "21") (name "/COMM15_RX3") (class "Default")
      (node (ref "PIN1") (pin "18") (pinfunction "18_18") (pintype "passive"))
    )
    (net (code "22") (name "/COMM16_TX2") (class "Default")
      (node (ref "PIN1") (pin "19") (pinfunction "19_19") (pintype "passive"))
    )
    (net (code "23") (name "/COMM17_RX2") (class "Default")
      (node (ref "PIN1") (pin "20") (pinfunction "20_20") (pintype "passive"))
    )
    (net (code "24") (name "/COMM18_TX1") (class "Default")
      (node (ref "PIN1") (pin "21") (pinfunction "21_21") (pintype "passive"))
    )
    (net (code "25") (name "/COMM19_RX1") (class "Default")
      (node (ref "PIN1") (pin "22") (pinfunction "22_22") (pintype "passive"))
    )
    (net (code "26") (name "/COMM20_SDA") (class "Default")
      (node (ref "PIC1") (pin "5") (pinfunction "RA2_5") (pintype "passive"))
      (node (ref "PIC2") (pin "5") (pinfunction "RA2_5") (pintype "passive"))
      (node (ref "PIC3") (pin "5") (pinfunction "RA2_5") (pintype "passive"))
      (node (ref "PIC4") (pin "5") (pinfunction "RA2_5") (pintype "passive"))
      (node (ref "PIN1") (pin "23") (pinfunction "23_23") (pintype "passive"))
    )
    (net (code "27") (name "/COMM21_SCL") (class "Default")
      (node (ref "PIC1") (pin "6") (pinfunction "RA1_6") (pintype "passive"))
      (node (ref "PIC2") (pin "6") (pinfunction "RA1_6") (pintype "passive"))
      (node (ref "PIC3") (pin "6") (pinfunction "RA1_6") (pintype "passive"))
      (node (ref "PIC4") (pin "6") (pinfunction "RA1_6") (pintype "passive"))
      (node (ref "PIN1") (pin "24") (pinfunction "24_24") (pintype "passive"))
    )
    (net (code "28") (name "/D22") (class "Default")
      (node (ref "PIN1") (pin "25") (pinfunction "25_25") (pintype "passive"))
    )
    (net (code "29") (name "/D23") (class "Default")
      (node (ref "PIN1") (pin "26") (pinfunction "26_26") (pintype "passive"))
    )
    (net (code "30") (name "/D24") (class "Default")
      (node (ref "PIN1") (pin "27") (pinfunction "27_27") (pintype "passive"))
    )
    (net (code "31") (name "/D25") (class "Default")
      (node (ref "PIN1") (pin "28") (pinfunction "28_28") (pintype "passive"))
    )
    (net (code "32") (name "/D26") (class "Default")
      (node (ref "PIN1") (pin "29") (pinfunction "29_29") (pintype "passive"))
    )
    (net (code "33") (name "/D27") (class "Default")
      (node (ref "PIN1") (pin "30") (pinfunction "30_30") (pintype "passive"))
    )
    (net (code "34") (name "/D28") (class "Default")
      (node (ref "PIN1") (pin "31") (pinfunction "31_31") (pintype "passive"))
    )
    (net (code "35") (name "/D29") (class "Default")
      (node (ref "PIN1") (pin "32") (pinfunction "32_32") (pintype "passive"))
    )
    (net (code "36") (name "/D30") (class "Default")
      (node (ref "PIN1") (pin "33") (pinfunction "33_33") (pintype "passive"))
    )
    (net (code "37") (name "/D31") (class "Default")
      (node (ref "PIN1") (pin "34") (pinfunction "34_34") (pintype "passive"))
    )
    (net (code "38") (name "/D32") (class "Default")
      (node (ref "PIN1") (pin "35") (pinfunction "35_35") (pintype "passive"))
    )
    (net (code "39") (name "/D33") (class "Default")
      (node (ref "PIN1") (pin "36") (pinfunction "36_36") (pintype "passive"))
    )
    (net (code "40") (name "/D34") (class "Default")
      (node (ref "PIN1") (pin "37") (pinfunction "37_37") (pintype "passive"))
    )
    (net (code "41") (name "/D35") (class "Default")
      (node (ref "PIN1") (pin "38") (pinfunction "38_38") (pintype "passive"))
    )
    (net (code "42") (name "/D36") (class "Default")
      (node (ref "PIN1") (pin "39") (pinfunction "39_39") (pintype "passive"))
    )
    (net (code "43") (name "/D37") (class "Default")
      (node (ref "PIN1") (pin "40") (pinfunction "40_40") (pintype "passive"))
    )
    (net (code "44") (name "/D38") (class "Default")
      (node (ref "PIN2") (pin "1") (pinfunction "1_1") (pintype "passive"))
    )
    (net (code "45") (name "/D39") (class "Default")
      (node (ref "PIN2") (pin "2") (pinfunction "2_2") (pintype "passive"))
    )
    (net (code "46") (name "/D40") (class "Default")
      (node (ref "PIN2") (pin "3") (pinfunction "3_3") (pintype "passive"))
    )
    (net (code "47") (name "/D41") (class "Default")
      (node (ref "PIN2") (pin "4") (pinfunction "4_4") (pintype "passive"))
    )
    (net (code "48") (name "/D42") (class "Default")
      (node (ref "PIN2") (pin "5") (pinfunction "5_5") (pintype "passive"))
    )
    (net (code "49") (name "/D43") (class "Default")
      (node (ref "PIN2") (pin "6") (pinfunction "6_6") (pintype "passive"))
    )
    (net (code "50") (name "/D44") (class "Default")
      (node (ref "PIN2") (pin "7") (pinfunction "7_7") (pintype "passive"))
    )
    (net (code "51") (name "/D45") (class "Default")
      (node (ref "PIN2") (pin "8") (pinfunction "8_8") (pintype "passive"))
    )
    (net (code "52") (name "/D46") (class "Default")
      (node (ref "PIN2") (pin "9") (pinfunction "9_9") (pintype "passive"))
    )
    (net (code "53") (name "/D47") (class "Default")
      (node (ref "PIN2") (pin "10") (pinfunction "10_10") (pintype "passive"))
    )
    (net (code "54") (name "/D48") (class "Default")
      (node (ref "PIN2") (pin "11") (pinfunction "11_11") (pintype "passive"))
    )
    (net (code "55") (name "/D49") (class "Default")
      (node (ref "PIN2") (pin "12") (pinfunction "12_12") (pintype "passive"))
    )
    (net (code "56") (name "/Enable1") (class "Default")
      (node (ref "PIC1") (pin "2") (pinfunction "RA5_2") (pintype "passive"))
      (node (ref "SW1A") (pin "5") (pinfunction "ON/OFF_5") (pintype "passive"))
      (node (ref "SW1B") (pin "5") (pinfunction "ON/OFF_5") (pintype "passive"))
    )
    (net (code "57") (name "/Enable2") (class "Default")
      (node (ref "PIC2") (pin "2") (pinfunction "RA5_2") (pintype "passive"))
      (node (ref "SW2A") (pin "5") (pinfunction "ON/OFF_5") (pintype "passive"))
      (node (ref "SW2B") (pin "5") (pinfunction "ON/OFF_5") (pintype "passive"))
    )
    (net (code "58") (name "/Enable3") (class "Default")
      (node (ref "PIC3") (pin "2") (pinfunction "RA5_2") (pintype "passive"))
      (node (ref "SW3A") (pin "5") (pinfunction "ON/OFF_5") (pintype "passive"))
      (node (ref "SW3B") (pin "5") (pinfunction "ON/OFF_5") (pintype "passive"))
    )
    (net (code "59") (name "/Enable4") (class "Default")
      (node (ref "PIC4") (pin "2") (pinfunction "RA5_2") (pintype "passive"))
      (node (ref "SW4A") (pin "5") (pinfunction "ON/OFF_5") (pintype "passive"))
      (node (ref "SW4B") (pin "5") (pinfunction "ON/OFF_5") (pintype "passive"))
    )
    (net (code "60") (name "/IN-A_3.3V") (class "Default")
      (node (ref "C37") (pin "2") (pinfunction "2_2") (pintype "passive"))
      (node (ref "J12") (pin "1") (pinfunction "1_1") (pintype "passive"))
      (node (ref "J20") (pin "2") (pinfunction "2_2") (pintype "passive"))
      (node (ref "R33") (pin "1") (pinfunction "1_1") (pintype "passive"))
      (node (ref "SW1A") (pin "4") (pinfunction "VIN_4") (pintype "passive"))
    )
    (net (code "61") (name "/IN-A_5V") (class "Default")
      (node (ref "C38") (pin "2") (pinfunction "2_2") (pintype "passive"))
      (node (ref "J13") (pin "1") (pinfunction "1_1") (pintype "passive"))
      (node (ref "J20") (pin "4") (pinfunction "4_4") (pintype "passive"))
      (node (ref "R34") (pin "2") (pinfunction "2_2") (pintype "passive"))
      (node (ref "SW1B") (pin "4") (pinfunction "VIN_4") (pintype "passive"))
    )
    (net (code "62") (name "/IN-B_3.3V") (class "Default")
      (node (ref "C39") (pin "2") (pinfunction "2_2") (pintype "passive"))
      (node (ref "J14") (pin "1") (pinfunction "1_1") (pintype "passive"))
      (node (ref "J21") (pin "2") (pinfunction "2_2") (pintype "passive"))
      (node (ref "R35") (pin "1") (pinfunction "1_1") (pintype "passive"))
      (node (ref "SW2A") (pin "4") (pinfunction "VIN_4") (pintype "passive"))
    )
    (net (code "63") (name "/IN-B_5V") (class "Default")
      (node (ref "C40") (pin "2") (pinfunction "2_2") (pintype "passive"))
      (node (ref "J15") (pin "1") (pinfunction "1_1") (pintype "passive"))
      (node (ref "J21") (pin "4") (pinfunction "4_4") (pintype "passive"))
      (node (ref "R36") (pin "2") (pinfunction "2_2") (pintype "passive"))
      (node (ref "SW2B") (pin "4") (pinfunction "VIN_4") (pintype "passive"))
    )
    (net (code "64") (name "/IN-C_3.3V") (class "Default")
      (node (ref "C41") (pin "1") (pinfunction "1_1") (pintype "passive"))
      (node (ref "J16") (pin "1") (pinfunction "1_1") (pintype "passive"))
      (node (ref "J22") (pin "2") (pinfunction "2_2") (pintype "passive"))
      (node (ref "R37") (pin "1") (pinfunction "1_1") (pintype "passive"))
      (node (ref "SW3A") (pin "4") (pinfunction "VIN_4") (pintype "passive"))
    )
    (net (code "65") (name "/IN-C_5V") (class "Default")
      (node (ref "C42") (pin "1") (pinfunction "1_1") (pintype "passive"))
      (node (ref "J17") (pin "1") (pinfunction "1_1") (pintype "passive"))
      (node (ref "J22") (pin "4") (pinfunction "4_4") (pintype "passive"))
      (node (ref "R38") (pin "2") (pinfunction "2_2") (pintype "passive"))
      (node (ref "SW3B") (pin "4") (pinfunction "VIN_4") (pintype "passive"))
    )
    (net (code "66") (name "/IN-D_3.3V") (class "Default")
      (node (ref "C43") (pin "2") (pinfunction "2_2") (pintype "passive"))
      (node (ref "J18") (pin "1") (pinfunction "1_1") (pintype "passive"))
      (node (ref "J23") (pin "2") (pinfunction "2_2") (pintype "passive"))
      (node (ref "R39") (pin "1") (pinfunction "1_1") (pintype "passive"))
      (node (ref "SW4A") (pin "4") (pinfunction "VIN_4") (pintype "passive"))
    )
    (net (code "67") (name "/IN-D_5V") (class "Default")
      (node (ref "C44") (pin "2") (pinfunction "2_2") (pintype "passive"))
      (node (ref "J19") (pin "1") (pinfunction "1_1") (pintype "passive"))
      (node (ref "J23") (pin "4") (pinfunction "4_4") (pintype "passive"))
      (node (ref "R40") (pin "2") (pinfunction "2_2") (pintype "passive"))
      (node (ref "SW4B") (pin "4") (pinfunction "VIN_4") (pintype "passive"))
    )
    (net (code "68") (name "/IN_3.3V") (class "Default")
      (node (ref "J20") (pin "1") (pinfunction "1_1") (pintype "passive"))
      (node (ref "J21") (pin "1") (pinfunction "1_1") (pintype "passive"))
      (node (ref "J22") (pin "1") (pinfunction "1_1") (pintype "passive"))
      (node (ref "J23") (pin "1") (pinfunction "1_1") (pintype "passive"))
      (node (ref "PIN2") (pin "35") (pinfunction "35_35") (pintype "passive"))
    )
    (net (code "69") (name "/IN_5V") (class "Default")
      (node (ref "C50") (pin "1") (pinfunction "1_1") (pintype "passive"))
      (node (ref "C51") (pin "1") (pinfunction "1_1") (pintype "passive"))
      (node (ref "C52") (pin "1") (pinfunction "1_1") (pintype "passive"))
      (node (ref "C53") (pin "1") (pinfunction "1_1") (pintype "passive"))
      (node (ref "J20") (pin "3") (pinfunction "3_3") (pintype "passive"))
      (node (ref "J21") (pin "3") (pinfunction "3_3") (pintype "passive"))
      (node (ref "J22") (pin "3") (pinfunction "3_3") (pintype "passive"))
      (node (ref "J23") (pin "3") (pinfunction "3_3") (pintype "passive"))
      (node (ref "PIC1") (pin "1") (pinfunction "Vdd_1") (pintype "passive"))
      (node (ref "PIC2") (pin "1") (pinfunction "Vdd_1") (pintype "passive"))
      (node (ref "PIC3") (pin "1") (pinfunction "Vdd_1") (pintype "passive"))
      (node (ref "PIC4") (pin "1") (pinfunction "Vdd_1") (pintype "passive"))
      (node (ref "PIN2") (pin "37") (pinfunction "37_37") (pintype "passive"))
      (node (ref "R50") (pin "2") (pinfunction "2_2") (pintype "passive"))
      (node (ref "R51") (pin "2") (pinfunction "2_2") (pintype "passive"))
      (node (ref "R52") (pin "2") (pinfunction "2_2") (pintype "passive"))
      (node (ref "R53") (pin "2") (pinfunction "2_2") (pintype "passive"))
    )
    (net (code "70") (name "/IOREF0") (class "Default")
      (node (ref "PIN2") (pin "34") (pinfunction "34_34") (pintype "passive"))
    )
    (net (code "71") (name "/IOREF1") (class "Default")
      (node (ref "PIN2") (pin "36") (pinfunction "36_36") (pintype "passive"))
    )
    (net (code "72") (name "/LU1A") (class "Default")
      (node (ref "LIM3") (pin "4") (pinfunction "FAULT/_4") (pintype "passive"))
      (node (ref "PIC1") (pin "3") (pinfunction "RA4_3") (pintype "passive"))
      (node (ref "R15") (pin "1") (pinfunction "1_1") (pintype "passive"))
    )
    (net (code "73") (name "/LU1B") (class "Default")
      (node (ref "LIM4") (pin "4") (pinfunction "FAULT/_4") (pintype "passive"))
      (node (ref "PIC1") (pin "4") (pinfunction "RA3_4") (pintype "passive"))
      (node (ref "R13") (pin "1") (pinfunction "1_1") (pintype "passive"))
    )
    (net (code "74") (name "/LU2A") (class "Default")
      (node (ref "LIM1") (pin "4") (pinfunction "FAULT/_4") (pintype "passive"))
      (node (ref "PIC2") (pin "3") (pinfunction "RA4_3") (pintype "passive"))
      (node (ref "R7") (pin "1") (pinfunction "1_1") (pintype "passive"))
    )
    (net (code "75") (name "/LU2B") (class "Default")
      (node (ref "LIM2") (pin "4") (pinfunction "FAULT/_4") (pintype "passive"))
      (node (ref "PIC2") (pin "4") (pinfunction "RA3_4") (pintype "passive"))
      (node (ref "R45") (pin "1") (pinfunction "1_1") (pintype "passive"))
    )
    (net (code "76") (name "/LU3A") (class "Default")
      (node (ref "LIM5") (pin "4") (pinfunction "FAULT/_4") (pintype "passive"))
      (node (ref "PIC3") (pin "3") (pinfunction "RA4_3") (pintype "passive"))
      (node (ref "R23") (pin "1") (pinfunction "1_1") (pintype "passive"))
    )
    (net (code "77") (name "/LU3B") (class "Default")
      (node (ref "LIM6") (pin "4") (pinfunction "FAULT/_4") (pintype "passive"))
      (node (ref "PIC3") (pin "4") (pinfunction "RA3_4") (pintype "passive"))
      (node (ref "R21") (pin "1") (pinfunction "1_1") (pintype "passive"))
    )
    (net (code "78") (name "/LU4A") (class "Default")
      (node (ref "LIM7") (pin "4") (pinfunction "FAULT/_4") (pintype "passive"))
      (node (ref "PIC4") (pin "3") (pinfunction "RA4_3") (pintype "passive"))
      (node (ref "R31") (pin "1") (pinfunction "1_1") (pintype "passive"))
    )
    (net (code "79") (name "/LU4B") (class "Default")
      (node (ref "LIM8") (pin "4") (pinfunction "FAULT/_4") (pintype "passive"))
      (node (ref "PIC4") (pin "4") (pinfunction "RA3_4") (pintype "passive"))
      (node (ref "R29") (pin "1") (pinfunction "1_1") (pintype "passive"))
    )
    (net (code "80") (name "/MISO") (class "Default")
      (node (ref "PIN2") (pin "13") (pinfunction "13_13") (pintype "passive"))
    )
    (net (code "81") (name "/MOSI") (class "Default")
      (node (ref "PIN2") (pin "14") (pinfunction "14_14") (pintype "passive"))
    )
    (net (code "82") (name "/OUT-A_3.3V") (class "Default")
      (node (ref "C18") (pin "1") (pinfunction "1_1") (pintype "passive"))
      (node (ref "J1") (pin "1") (pinfunction "1_1") (pintype "passive"))
      (node (ref "LIM3") (pin "6") (pinfunction "VOUT_6") (pintype "passive"))
    )
    (net (code "83") (name "/OUT-A_5V") (class "Default")
      (node (ref "C16") (pin "1") (pinfunction "1_1") (pintype "passive"))
      (node (ref "J2") (pin "1") (pinfunction "1_1") (pintype "passive"))
      (node (ref "LIM4") (pin "6") (pinfunction "VOUT_6") (pintype "passive"))
    )
    (net (code "84") (name "/OUT-B_3.3V") (class "Default")
      (node (ref "C9") (pin "1") (pinfunction "1_1") (pintype "passive"))
      (node (ref "J3") (pin "1") (pinfunction "1_1") (pintype "passive"))
      (node (ref "LIM1") (pin "6") (pinfunction "VOUT_6") (pintype "passive"))
    )
    (net (code "85") (name "/OUT-B_5V") (class "Default")
      (node (ref "C7") (pin "1") (pinfunction "1_1") (pintype "passive"))
      (node (ref "J4") (pin "1") (pinfunction "1_1") (pintype "passive"))
      (node (ref "LIM2") (pin "6") (pinfunction "VOUT_6") (pintype "passive"))
    )
    (net (code "86") (name "/OUT-C_3.3V") (class "Default")
      (node (ref "C27") (pin "1") (pinfunction "1_1") (pintype "passive"))
      (node (ref "J5") (pin "1") (pinfunction "1_1") (pintype "passive"))
      (node (ref "LIM5") (pin "6") (pinfunction "VOUT_6") (pintype "passive"))
    )
    (net (code "87") (name "/OUT-C_5V") (class "Default")
      (node (ref "C25") (pin "1") (pinfunction "1_1") (pintype "passive"))
      (node (ref "J6") (pin "1") (pinfunction "1_1") (pintype "passive"))
      (node (ref "LIM6") (pin "6") (pinfunction "VOUT_6") (pintype "passive"))
    )
    (net (code "88") (name "/OUT-D_3.3V") (class "Default")
      (node (ref "C36") (pin "1") (pinfunction "1_1") (pintype "passive"))
      (node (ref "J7") (pin "1") (pinfunction "1_1") (pintype "passive"))
      (node (ref "LIM7") (pin "6") (pinfunction "VOUT_6") (pintype "passive"))
    )
    (net (code "89") (name "/OUT-D_5V") (class "Default")
      (node (ref "C34") (pin "1") (pinfunction "1_1") (pintype "passive"))
      (node (ref "J8") (pin "1") (pinfunction "1_1") (pintype "passive"))
      (node (ref "LIM8") (pin "6") (pinfunction "VOUT_6") (pintype "passive"))
    )
    (net (code "90") (name "/PWM2") (class "Default")
      (node (ref "PIN1") (pin "13") (pinfunction "13_13") (pintype "passive"))
    )
    (net (code "91") (name "/PWM3") (class "Default")
      (node (ref "PIN1") (pin "14") (pinfunction "14_14") (pintype "passive"))
    )
    (net (code "92") (name "/PWM4") (class "Default")
      (node (ref "PIN1") (pin "11") (pinfunction "11_11") (pintype "passive"))
    )
    (net (code "93") (name "/PWM5") (class "Default")
      (node (ref "PIN1") (pin "12") (pinfunction "12_12") (pintype "passive"))
    )
    (net (code "94") (name "/PWM6") (class "Default")
      (node (ref "PIN1") (pin "9") (pinfunction "9_9") (pintype "passive"))
    )
    (net (code "95") (name "/PWM7") (class "Default")
      (node (ref "PIN1") (pin "10") (pinfunction "10_10") (pintype "passive"))
    )
    (net (code "96") (name "/PWM8") (class "Default")
      (node (ref "PIN1") (pin "7") (pinfunction "7_7") (pintype "passive"))
    )
    (net (code "97") (name "/PWM9") (class "Default")
      (node (ref "PIN1") (pin "8") (pinfunction "8_8") (pintype "passive"))
    )
    (net (code "98") (name "/PWM10") (class "Default")
      (node (ref "PIN1") (pin "5") (pinfunction "5_5") (pintype "passive"))
    )
    (net (code "99") (name "/PWM11") (class "Default")
      (node (ref "PIN1") (pin "6") (pinfunction "6_6") (pintype "passive"))
    )
    (net (code "100") (name "/PWM12") (class "Default")
      (node (ref "PIN1") (pin "3") (pinfunction "3_3") (pintype "passive"))
    )
    (net (code "101") (name "/PWM13") (class "Default")
      (node (ref "PIN1") (pin "4") (pinfunction "4_4") (pintype "passive"))
    )
    (net (code "102") (name "/RST") (class "Default")
      (node (ref "PIN1") (pin "2") (pinfunction "2_2") (pintype "passive"))
    )
    (net (code "103") (name "/SCK") (class "Default")
      (node (ref "PIN2") (pin "15") (pinfunction "15_15") (pintype "passive"))
    )
    (net (code "104") (name "/SS") (class "Default")
      (node (ref "PIN2") (pin "16") (pinfunction "16_16") (pintype "passive"))
    )
    (net (code "105") (name "/VIN") (class "Default")
      (node (ref "PIN2") (pin "33") (pinfunction "33_33") (pintype "passive"))
    )
    (net (code "106") (name "GND") (class "Default")
      (node (ref "C1") (pin "2") (pinfunction "2_2") (pintype "passive"))
      (node (ref "C10") (pin "2") (pinfunction "2_2") (pintype "passive"))
      (node (ref "C11") (pin "2") (pinfunction "2_2") (pintype "passive"))
      (node (ref "C12") (pin "1") (pinfunction "1_1") (pintype "passive"))
      (node (ref "C13") (pin "1") (pinfunction "1_1") (pintype "passive"))
      (node (ref "C15") (pin "2") (pinfunction "2_2") (pintype "passive"))
      (node (ref "C16") (pin "2") (pinfunction "2_2") (pintype "passive"))
      (node (ref "C17") (pin "2") (pinfunction "2_2") (pintype "passive"))
      (node (ref "C18") (pin "2") (pinfunction "2_2") (pintype "passive"))
      (node (ref "C19") (pin "2") (pinfunction "2_2") (pintype "passive"))
      (node (ref "C2") (pin "2") (pinfunction "2_2") (pintype "passive"))
      (node (ref "C20") (pin "2") (pinfunction "2_2") (pintype "passive"))
      (node (ref "C21") (pin "2") (pinfunction "2_2") (pintype "passive"))
      (node (ref "C22") (pin "1") (pinfunction "1_1") (pintype "passive"))
      (node (ref "C24") (pin "2") (pinfunction "2_2") (pintype "passive"))
      (node (ref "C25") (pin "2") (pinfunction "2_2") (pintype "passive"))
      (node (ref "C26") (pin "2") (pinfunction "2_2") (pintype "passive"))
      (node (ref "C27") (pin "2") (pinfunction "2_2") (pintype "passive"))
      (node (ref "C28") (pin "2") (pinfunction "2_2") (pintype "passive"))
      (node (ref "C29") (pin "2") (pinfunction "2_2") (pintype "passive"))
      (node (ref "C3") (pin "2") (pinfunction "2_2") (pintype "passive"))
      (node (ref "C30") (pin "2") (pinfunction "2_2") (pintype "passive"))
      (node (ref "C31") (pin "1") (pinfunction "1_1") (pintype "passive"))
      (node (ref "C33") (pin "2") (pinfunction "2_2") (pintype "passive"))
      (node (ref "C34") (pin "2") (pinfunction "2_2") (pintype "passive"))
      (node (ref "C35") (pin "2") (pinfunction "2_2") (pintype "passive"))
      (node (ref "C36") (pin "2") (pinfunction "2_2") (pintype "passive"))
      (node (ref "C37") (pin "1") (pinfunction "1_1") (pintype "passive"))
      (node (ref "C38") (pin "1") (pinfunction "1_1") (pintype "passive"))
      (node (ref "C39") (pin "1") (pinfunction "1_1") (pintype "passive"))
      (node (ref "C4") (pin "1") (pinfunction "1_1") (pintype "passive"))
      (node (ref "C40") (pin "1") (pinfunction "1_1") (pintype "passive"))
      (node (ref "C41") (pin "2") (pinfunction "2_2") (pintype "passive"))
      (node (ref "C42") (pin "2") (pinfunction "2_2") (pintype "passive"))
      (node (ref "C43") (pin "1") (pinfunction "1_1") (pintype "passive"))
      (node (ref "C44") (pin "1") (pinfunction "1_1") (pintype "passive"))
      (node (ref "C50") (pin "2") (pinfunction "2_2") (pintype "passive"))
      (node (ref "C51") (pin "2") (pinfunction "2_2") (pintype "passive"))
      (node (ref "C52") (pin "2") (pinfunction "2_2") (pintype "passive"))
      (node (ref "C53") (pin "2") (pinfunction "2_2") (pintype "passive"))
      (node (ref "C6") (pin "2") (pinfunction "2_2") (pintype "passive"))
      (node (ref "C7") (pin "2") (pinfunction "2_2") (pintype "passive"))
      (node (ref "C8") (pin "2") (pinfunction "2_2") (pintype "passive"))
      (node (ref "C9") (pin "2") (pinfunction "2_2") (pintype "passive"))
      (node (ref "DCDC1") (pin "12") (pinfunction "GND_12") (pintype "passive"))
      (node (ref "DCDC1") (pin "18") (pinfunction "MID_18") (pintype "passive"))
      (node (ref "DCDC1") (pin "2") (pinfunction "GND_2") (pintype "passive"))
      (node (ref "DCDC1") (pin "3") (pinfunction "GND_3") (pintype "passive"))
      (node (ref "DCDC2") (pin "12") (pinfunction "GND_12") (pintype "passive"))
      (node (ref "DCDC2") (pin "18") (pinfunction "MID_18") (pintype "passive"))
      (node (ref "DCDC2") (pin "2") (pinfunction "GND_2") (pintype "passive"))
      (node (ref "DCDC2") (pin "3") (pinfunction "GND_3") (pintype "passive"))
      (node (ref "DCDC3") (pin "12") (pinfunction "GND_12") (pintype "passive"))
      (node (ref "DCDC3") (pin "18") (pinfunction "MID_18") (pintype "passive"))
      (node (ref "DCDC3") (pin "2") (pinfunction "GND_2") (pintype "passive"))
      (node (ref "DCDC3") (pin "3") (pinfunction "GND_3") (pintype "passive"))
      (node (ref "DCDC4") (pin "12") (pinfunction "GND_12") (pintype "passive"))
      (node (ref "DCDC4") (pin "18") (pinfunction "MID_18") (pintype "passive"))
      (node (ref "DCDC4") (pin "2") (pinfunction "GND_2") (pintype "passive"))
      (node (ref "DCDC4") (pin "3") (pinfunction "GND_3") (pintype "passive"))
      (node (ref "LIM1") (pin "2") (pinfunction "GND_2") (pintype "passive"))
      (node (ref "LIM2") (pin "2") (pinfunction "GND_2") (pintype "passive"))
      (node (ref "LIM3") (pin "2") (pinfunction "GND_2") (pintype "passive"))
      (node (ref "LIM4") (pin "2") (pinfunction "GND_2") (pintype "passive"))
      (node (ref "LIM5") (pin "2") (pinfunction "GND_2") (pintype "passive"))
      (node (ref "LIM6") (pin "2") (pinfunction "GND_2") (pintype "passive"))
      (node (ref "LIM7") (pin "2") (pinfunction "GND_2") (pintype "passive"))
      (node (ref "LIM8") (pin "2") (pinfunction "GND_2") (pintype "passive"))
      (node (ref "PIC1") (pin "8") (pinfunction "Vss_8") (pintype "passive"))
      (node (ref "PIC2") (pin "8") (pinfunction "Vss_8") (pintype "passive"))
      (node (ref "PIC3") (pin "8") (pinfunction "Vss_8") (pintype "passive"))
      (node (ref "PIC4") (pin "8") (pinfunction "Vss_8") (pintype "passive"))
      (node (ref "PIN2") (pin "39") (pinfunction "39_39") (pintype "passive"))
      (node (ref "POT1") (pin "2") (pinfunction "C_2") (pintype "passive"))
      (node (ref "POT1") (pin "3") (pinfunction "B_3") (pintype "passive"))
      (node (ref "POT10") (pin "2") (pinfunction "C_2") (pintype "passive"))
      (node (ref "POT10") (pin "3") (pinfunction "B_3") (pintype "passive"))
      (node (ref "POT12") (pin "2") (pinfunction "C_2") (pintype "passive"))
      (node (ref "POT12") (pin "3") (pinfunction "B_3") (pintype "passive"))
      (node (ref "POT3") (pin "2") (pinfunction "C_2") (pintype "passive"))
      (node (ref "POT3") (pin "3") (pinfunction "B_3") (pintype "passive"))
      (node (ref "POT4") (pin "2") (pinfunction "C_2") (pintype "passive"))
      (node (ref "POT4") (pin "3") (pinfunction "B_3") (pintype "passive"))
      (node (ref "POT6") (pin "2") (pinfunction "C_2") (pintype "passive"))
      (node (ref "POT6") (pin "3") (pinfunction "B_3") (pintype "passive"))
      (node (ref "POT7") (pin "2") (pinfunction "C_2") (pintype "passive"))
      (node (ref "POT7") (pin "3") (pinfunction "B_3") (pintype "passive"))
      (node (ref "POT9") (pin "2") (pinfunction "C_2") (pintype "passive"))
      (node (ref "POT9") (pin "3") (pinfunction "B_3") (pintype "passive"))
      (node (ref "R1") (pin "1") (pinfunction "1_1") (pintype "passive"))
      (node (ref "R12") (pin "1") (pinfunction "1_1") (pintype "passive"))
      (node (ref "R17") (pin "1") (pinfunction "1_1") (pintype "passive"))
      (node (ref "R2") (pin "1") (pinfunction "1_1") (pintype "passive"))
      (node (ref "R20") (pin "1") (pinfunction "1_1") (pintype "passive"))
      (node (ref "R25") (pin "1") (pinfunction "1_1") (pintype "passive"))
      (node (ref "R28") (pin "1") (pinfunction "1_1") (pintype "passive"))
      (node (ref "R3") (pin "1") (pinfunction "1_1") (pintype "passive"))
      (node (ref "R4") (pin "1") (pinfunction "1_1") (pintype "passive"))
      (node (ref "R46") (pin "1") (pinfunction "1_1") (pintype "passive"))
      (node (ref "R5") (pin "1") (pinfunction "1_1") (pintype "passive"))
      (node (ref "R9") (pin "1") (pinfunction "1_1") (pintype "passive"))
      (node (ref "SW1A") (pin "1") (pinfunction "GND_1") (pintype "passive"))
      (node (ref "SW1B") (pin "1") (pinfunction "GND_1") (pintype "passive"))
      (node (ref "SW2A") (pin "1") (pinfunction "GND_1") (pintype "passive"))
      (node (ref "SW2B") (pin "1") (pinfunction "GND_1") (pintype "passive"))
      (node (ref "SW3A") (pin "1") (pinfunction "GND_1") (pintype "passive"))
      (node (ref "SW3B") (pin "1") (pinfunction "GND_1") (pintype "passive"))
      (node (ref "SW4A") (pin "1") (pinfunction "GND_1") (pintype "passive"))
      (node (ref "SW4B") (pin "1") (pinfunction "GND_1") (pintype "passive"))
    )
    (net (code "107") (name "Net-(DCDC1-FB)") (class "Default")
      (node (ref "DCDC1") (pin "16") (pinfunction "FB_16") (pintype "passive"))
      (node (ref "R3") (pin "2") (pinfunction "2_2") (pintype "passive"))
      (node (ref "R42") (pin "1") (pinfunction "1_1") (pintype "passive"))
    )
    (net (code "108") (name "Net-(DCDC1-MAXV)") (class "Default")
      (node (ref "DCDC1") (pin "15") (pinfunction "MAXV_15") (pintype "passive"))
      (node (ref "R1") (pin "2") (pinfunction "2_2") (pintype "passive"))
    )
    (net (code "109") (name "Net-(DCDC1-PFI)") (class "Default")
      (node (ref "C2") (pin "1") (pinfunction "1_1") (pintype "passive"))
      (node (ref "DCDC1") (pin "11") (pinfunction "VIN_11") (pintype "passive"))
      (node (ref "DCDC1") (pin "14") (pinfunction "PFI_14") (pintype "passive"))
      (node (ref "DCDC1") (pin "7") (pinfunction "RUN_7") (pintype "passive"))
      (node (ref "SW2B") (pin "2") (pinfunction "VOUT_2") (pintype "passive"))
      (node (ref "SW2B") (pin "3") (pinfunction "VOUT_3") (pintype "passive"))
    )
    (net (code "110") (name "Net-(DCDC1-PROG)") (class "Default")
      (node (ref "C3") (pin "1") (pinfunction "1_1") (pintype "passive"))
      (node (ref "DCDC1") (pin "8") (pinfunction "PROG_8") (pintype "passive"))
      (node (ref "R4") (pin "2") (pinfunction "2_2") (pintype "passive"))
    )
    (net (code "111") (name "Net-(DCDC1-RSENP)") (class "Default")
      (node (ref "C1") (pin "1") (pinfunction "1_1") (pintype "passive"))
      (node (ref "DCDC1") (pin "5") (pinfunction "RSENP_5") (pintype "passive"))
      (node (ref "DCDC1") (pin "6") (pinfunction "RSENS_6") (pintype "passive"))
    )
    (net (code "112") (name "Net-(DCDC1-SW1-Pad1)") (class "Default")
      (node (ref "DCDC1") (pin "1") (pinfunction "SW1_1") (pintype "passive"))
      (node (ref "DCDC1") (pin "4") (pinfunction "SW1_4") (pintype "passive"))
      (node (ref "L1") (pin "1") (pinfunction "1_1") (pintype "passive"))
    )
    (net (code "113") (name "Net-(DCDC1-SW2-Pad23)") (class "Default")
      (node (ref "DCDC1") (pin "23") (pinfunction "SW2_23") (pintype "passive"))
      (node (ref "DCDC1") (pin "24") (pinfunction "SW2_24") (pintype "passive"))
      (node (ref "L1") (pin "2") (pinfunction "2_2") (pintype "passive"))
    )
    (net (code "114") (name "Net-(DCDC1-VOUTS)") (class "Default")
      (node (ref "C13") (pin "2") (pinfunction "2_2") (pintype "passive"))
      (node (ref "C6") (pin "1") (pinfunction "1_1") (pintype "passive"))
      (node (ref "DCDC1") (pin "19") (pinfunction "VOUTS_19") (pintype "passive"))
      (node (ref "DCDC1") (pin "20") (pinfunction "VOUTP_20") (pintype "passive"))
      (node (ref "DCDC1") (pin "21") (pinfunction "VOUTP_21") (pintype "passive"))
      (node (ref "LIM2") (pin "1") (pinfunction "Vin_1") (pintype "passive"))
      (node (ref "LIM2") (pin "3") (pinfunction "EN_3") (pintype "passive"))
      (node (ref "POT5") (pin "1") (pinfunction "A_1") (pintype "passive"))
      (node (ref "R45") (pin "2") (pinfunction "2_2") (pintype "passive"))
    )
    (net (code "115") (name "Net-(DCDC2-FB)") (class "Default")
      (node (ref "DCDC2") (pin "16") (pinfunction "FB_16") (pintype "passive"))
      (node (ref "R2") (pin "2") (pinfunction "2_2") (pintype "passive"))
      (node (ref "R41") (pin "1") (pinfunction "1_1") (pintype "passive"))
    )
    (net (code "116") (name "Net-(DCDC2-MAXV)") (class "Default")
      (node (ref "DCDC2") (pin "15") (pinfunction "MAXV_15") (pintype "passive"))
      (node (ref "R9") (pin "2") (pinfunction "2_2") (pintype "passive"))
    )
    (net (code "117") (name "Net-(DCDC2-PFI)") (class "Default")
      (node (ref "C11") (pin "1") (pinfunction "1_1") (pintype "passive"))
      (node (ref "DCDC2") (pin "11") (pinfunction "VIN_11") (pintype "passive"))
      (node (ref "DCDC2") (pin "14") (pinfunction "PFI_14") (pintype "passive"))
      (node (ref "DCDC2") (pin "7") (pinfunction "RUN_7") (pintype "passive"))
      (node (ref "SW1B") (pin "2") (pinfunction "VOUT_2") (pintype "passive"))
      (node (ref "SW1B") (pin "3") (pinfunction "VOUT_3") (pintype "passive"))
    )
    (net (code "118") (name "Net-(DCDC2-PROG)") (class "Default")
      (node (ref "C12") (pin "2") (pinfunction "2_2") (pintype "passive"))
      (node (ref "DCDC2") (pin "8") (pinfunction "PROG_8") (pintype "passive"))
      (node (ref "R12") (pin "2") (pinfunction "2_2") (pintype "passive"))
    )
    (net (code "119") (name "Net-(DCDC2-RSENP)") (class "Default")
      (node (ref "C10") (pin "1") (pinfunction "1_1") (pintype "passive"))
      (node (ref "DCDC2") (pin "5") (pinfunction "RSENP_5") (pintype "passive"))
      (node (ref "DCDC2") (pin "6") (pinfunction "RSENS_6") (pintype "passive"))
    )
    (net (code "120") (name "Net-(DCDC2-SW1-Pad1)") (class "Default")
      (node (ref "DCDC2") (pin "1") (pinfunction "SW1_1") (pintype "passive"))
      (node (ref "DCDC2") (pin "4") (pinfunction "SW1_4") (pintype "passive"))
      (node (ref "L2") (pin "1") (pinfunction "1_1") (pintype "passive"))
    )
    (net (code "121") (name "Net-(DCDC2-SW2-Pad23)") (class "Default")
      (node (ref "DCDC2") (pin "23") (pinfunction "SW2_23") (pintype "passive"))
      (node (ref "DCDC2") (pin "24") (pinfunction "SW2_24") (pintype "passive"))
      (node (ref "L2") (pin "2") (pinfunction "2_2") (pintype "passive"))
    )
    (net (code "122") (name "Net-(DCDC2-VOUTS)") (class "Default")
      (node (ref "C15") (pin "1") (pinfunction "1_1") (pintype "passive"))
      (node (ref "C4") (pin "2") (pinfunction "2_2") (pintype "passive"))
      (node (ref "DCDC2") (pin "19") (pinfunction "VOUTS_19") (pintype "passive"))
      (node (ref "DCDC2") (pin "20") (pinfunction "VOUTP_20") (pintype "passive"))
      (node (ref "DCDC2") (pin "21") (pinfunction "VOUTP_21") (pintype "passive"))
      (node (ref "LIM4") (pin "1") (pinfunction "Vin_1") (pintype "passive"))
      (node (ref "LIM4") (pin "3") (pinfunction "EN_3") (pintype "passive"))
      (node (ref "POT2") (pin "1") (pinfunction "A_1") (pintype "passive"))
      (node (ref "R13") (pin "2") (pinfunction "2_2") (pintype "passive"))
    )
    (net (code "123") (name "Net-(DCDC3-FB)") (class "Default")
      (node (ref "DCDC3") (pin "16") (pinfunction "FB_16") (pintype "passive"))
      (node (ref "R43") (pin "1") (pinfunction "1_1") (pintype "passive"))
      (node (ref "R46") (pin "2") (pinfunction "2_2") (pintype "passive"))
    )
    (net (code "124") (name "Net-(DCDC3-MAXV)") (class "Default")
      (node (ref "DCDC3") (pin "15") (pinfunction "MAXV_15") (pintype "passive"))
      (node (ref "R17") (pin "2") (pinfunction "2_2") (pintype "passive"))
    )
    (net (code "125") (name "Net-(DCDC3-PFI)") (class "Default")
      (node (ref "C20") (pin "1") (pinfunction "1_1") (pintype "passive"))
      (node (ref "DCDC3") (pin "11") (pinfunction "VIN_11") (pintype "passive"))
      (node (ref "DCDC3") (pin "14") (pinfunction "PFI_14") (pintype "passive"))
      (node (ref "DCDC3") (pin "7") (pinfunction "RUN_7") (pintype "passive"))
      (node (ref "SW3B") (pin "2") (pinfunction "VOUT_2") (pintype "passive"))
      (node (ref "SW3B") (pin "3") (pinfunction "VOUT_3") (pintype "passive"))
    )
    (net (code "126") (name "Net-(DCDC3-PROG)") (class "Default")
      (node (ref "C21") (pin "1") (pinfunction "1_1") (pintype "passive"))
      (node (ref "DCDC3") (pin "8") (pinfunction "PROG_8") (pintype "passive"))
      (node (ref "R20") (pin "2") (pinfunction "2_2") (pintype "passive"))
    )
    (net (code "127") (name "Net-(DCDC3-RSENP)") (class "Default")
      (node (ref "C19") (pin "1") (pinfunction "1_1") (pintype "passive"))
      (node (ref "DCDC3") (pin "5") (pinfunction "RSENP_5") (pintype "passive"))
      (node (ref "DCDC3") (pin "6") (pinfunction "RSENS_6") (pintype "passive"))
    )
    (net (code "128") (name "Net-(DCDC3-SW1-Pad1)") (class "Default")
      (node (ref "DCDC3") (pin "1") (pinfunction "SW1_1") (pintype "passive"))
      (node (ref "DCDC3") (pin "4") (pinfunction "SW1_4") (pintype "passive"))
      (node (ref "L3") (pin "1") (pinfunction "1_1") (pintype "passive"))
    )
    (net (code "129") (name "Net-(DCDC3-SW2-Pad23)") (class "Default")
      (node (ref "DCDC3") (pin "23") (pinfunction "SW2_23") (pintype "passive"))
      (node (ref "DCDC3") (pin "24") (pinfunction "SW2_24") (pintype "passive"))
      (node (ref "L3") (pin "2") (pinfunction "2_2") (pintype "passive"))
    )
    (net (code "130") (name "Net-(DCDC3-VOUTS)") (class "Default")
      (node (ref "C22") (pin "2") (pinfunction "2_2") (pintype "passive"))
      (node (ref "C24") (pin "1") (pinfunction "1_1") (pintype "passive"))
      (node (ref "DCDC3") (pin "19") (pinfunction "VOUTS_19") (pintype "passive"))
      (node (ref "DCDC3") (pin "20") (pinfunction "VOUTP_20") (pintype "passive"))
      (node (ref "DCDC3") (pin "21") (pinfunction "VOUTP_21") (pintype "passive"))
      (node (ref "LIM6") (pin "1") (pinfunction "Vin_1") (pintype "passive"))
      (node (ref "LIM6") (pin "3") (pinfunction "EN_3") (pintype "passive"))
      (node (ref "POT8") (pin "1") (pinfunction "A_1") (pintype "passive"))
      (node (ref "R21") (pin "2") (pinfunction "2_2") (pintype "passive"))
    )
    (net (code "131") (name "Net-(DCDC4-FB)") (class "Default")
      (node (ref "DCDC4") (pin "16") (pinfunction "FB_16") (pintype "passive"))
      (node (ref "R44") (pin "1") (pinfunction "1_1") (pintype "passive"))
      (node (ref "R5") (pin "2") (pinfunction "2_2") (pintype "passive"))
    )
    (net (code "132") (name "Net-(DCDC4-MAXV)") (class "Default")
      (node (ref "DCDC4") (pin "15") (pinfunction "MAXV_15") (pintype "passive"))
      (node (ref "R25") (pin "2") (pinfunction "2_2") (pintype "passive"))
    )
    (net (code "133") (name "Net-(DCDC4-PFI)") (class "Default")
      (node (ref "C29") (pin "1") (pinfunction "1_1") (pintype "passive"))
      (node (ref "DCDC4") (pin "11") (pinfunction "VIN_11") (pintype "passive"))
      (node (ref "DCDC4") (pin "14") (pinfunction "PFI_14") (pintype "passive"))
      (node (ref "DCDC4") (pin "7") (pinfunction "RUN_7") (pintype "passive"))
      (node (ref "SW4B") (pin "2") (pinfunction "VOUT_2") (pintype "passive"))
      (node (ref "SW4B") (pin "3") (pinfunction "VOUT_3") (pintype "passive"))
    )
    (net (code "134") (name "Net-(DCDC4-PROG)") (class "Default")
      (node (ref "C30") (pin "1") (pinfunction "1_1") (pintype "passive"))
      (node (ref "DCDC4") (pin "8") (pinfunction "PROG_8") (pintype "passive"))
      (node (ref "R28") (pin "2") (pinfunction "2_2") (pintype "passive"))
    )
    (net (code "135") (name "Net-(DCDC4-RSENP)") (class "Default")
      (node (ref "C28") (pin "1") (pinfunction "1_1") (pintype "passive"))
      (node (ref "DCDC4") (pin "5") (pinfunction "RSENP_5") (pintype "passive"))
      (node (ref "DCDC4") (pin "6") (pinfunction "RSENS_6") (pintype "passive"))
    )
    (net (code "136") (name "Net-(DCDC4-SW1-Pad1)") (class "Default")
      (node (ref "DCDC4") (pin "1") (pinfunction "SW1_1") (pintype "passive"))
      (node (ref "DCDC4") (pin "4") (pinfunction "SW1_4") (pintype "passive"))
      (node (ref "L4") (pin "1") (pinfunction "1_1") (pintype "passive"))
    )
    (net (code "137") (name "Net-(DCDC4-SW2-Pad23)") (class "Default")
      (node (ref "DCDC4") (pin "23") (pinfunction "SW2_23") (pintype "passive"))
      (node (ref "DCDC4") (pin "24") (pinfunction "SW2_24") (pintype "passive"))
      (node (ref "L4") (pin "2") (pinfunction "2_2") (pintype "passive"))
    )
    (net (code "138") (name "Net-(DCDC4-VOUTS)") (class "Default")
      (node (ref "C31") (pin "2") (pinfunction "2_2") (pintype "passive"))
      (node (ref "C33") (pin "1") (pinfunction "1_1") (pintype "passive"))
      (node (ref "DCDC4") (pin "19") (pinfunction "VOUTS_19") (pintype "passive"))
      (node (ref "DCDC4") (pin "20") (pinfunction "VOUTP_20") (pintype "passive"))
      (node (ref "DCDC4") (pin "21") (pinfunction "VOUTP_21") (pintype "passive"))
      (node (ref "LIM8") (pin "1") (pinfunction "Vin_1") (pintype "passive"))
      (node (ref "LIM8") (pin "3") (pinfunction "EN_3") (pintype "passive"))
      (node (ref "POT11") (pin "1") (pinfunction "A_1") (pintype "passive"))
      (node (ref "R29") (pin "2") (pinfunction "2_2") (pintype "passive"))
    )
    (net (code "139") (name "Net-(LIM1-EN)") (class "Default")
      (node (ref "C8") (pin "1") (pinfunction "1_1") (pintype "passive"))
      (node (ref "LIM1") (pin "1") (pinfunction "Vin_1") (pintype "passive"))
      (node (ref "LIM1") (pin "3") (pinfunction "EN_3") (pintype "passive"))
      (node (ref "R7") (pin "2") (pinfunction "2_2") (pintype "passive"))
      (node (ref "SW2A") (pin "2") (pinfunction "VOUT_2") (pintype "passive"))
      (node (ref "SW2A") (pin "3") (pinfunction "VOUT_3") (pintype "passive"))
    )
    (net (code "140") (name "Net-(LIM1-ILIMIT)") (class "Default")
      (node (ref "LIM1") (pin "5") (pinfunction "ILIMIT_5") (pintype "passive"))
      (node (ref "POT4") (pin "1") (pinfunction "A_1") (pintype "passive"))
    )
    (net (code "141") (name "Net-(LIM2-ILIMIT)") (class "Default")
      (node (ref "LIM2") (pin "5") (pinfunction "ILIMIT_5") (pintype "passive"))
      (node (ref "POT6") (pin "1") (pinfunction "A_1") (pintype "passive"))
    )
    (net (code "142") (name "Net-(LIM3-EN)") (class "Default")
      (node (ref "C17") (pin "1") (pinfunction "1_1") (pintype "passive"))
      (node (ref "LIM3") (pin "1") (pinfunction "Vin_1") (pintype "passive"))
      (node (ref "LIM3") (pin "3") (pinfunction "EN_3") (pintype "passive"))
      (node (ref "R15") (pin "2") (pinfunction "2_2") (pintype "passive"))
      (node (ref "SW1A") (pin "2") (pinfunction "VOUT_2") (pintype "passive"))
      (node (ref "SW1A") (pin "3") (pinfunction "VOUT_3") (pintype "passive"))
    )
    (net (code "143") (name "Net-(LIM3-ILIMIT)") (class "Default")
      (node (ref "LIM3") (pin "5") (pinfunction "ILIMIT_5") (pintype "passive"))
      (node (ref "POT1") (pin "1") (pinfunction "A_1") (pintype "passive"))
    )
    (net (code "144") (name "Net-(LIM4-ILIMIT)") (class "Default")
      (node (ref "LIM4") (pin "5") (pinfunction "ILIMIT_5") (pintype "passive"))
      (node (ref "POT3") (pin "1") (pinfunction "A_1") (pintype "passive"))
    )
    (net (code "145") (name "Net-(LIM5-EN)") (class "Default")
      (node (ref "C26") (pin "1") (pinfunction "1_1") (pintype "passive"))
      (node (ref "LIM5") (pin "1") (pinfunction "Vin_1") (pintype "passive"))
      (node (ref "LIM5") (pin "3") (pinfunction "EN_3") (pintype "passive"))
      (node (ref "R23") (pin "2") (pinfunction "2_2") (pintype "passive"))
      (node (ref "SW3A") (pin "2") (pinfunction "VOUT_2") (pintype "passive"))
      (node (ref "SW3A") (pin "3") (pinfunction "VOUT_3") (pintype "passive"))
    )
    (net (code "146") (name "Net-(LIM5-ILIMIT)") (class "Default")
      (node (ref "LIM5") (pin "5") (pinfunction "ILIMIT_5") (pintype "passive"))
      (node (ref "POT7") (pin "1") (pinfunction "A_1") (pintype "passive"))
    )
    (net (code "147") (name "Net-(LIM6-ILIMIT)") (class "Default")
      (node (ref "LIM6") (pin "5") (pinfunction "ILIMIT_5") (pintype "passive"))
      (node (ref "POT9") (pin "1") (pinfunction "A_1") (pintype "passive"))
    )
    (net (code "148") (name "Net-(LIM7-EN)") (class "Default")
      (node (ref "C35") (pin "1") (pinfunction "1_1") (pintype "passive"))
      (node (ref "LIM7") (pin "1") (pinfunction "Vin_1") (pintype "passive"))
      (node (ref "LIM7") (pin "3") (pinfunction "EN_3") (pintype "passive"))
      (node (ref "R31") (pin "2") (pinfunction "2_2") (pintype "passive"))
      (node (ref "SW4A") (pin "2") (pinfunction "VOUT_2") (pintype "passive"))
      (node (ref "SW4A") (pin "3") (pinfunction "VOUT_3") (pintype "passive"))
    )
    (net (code "149") (name "Net-(LIM7-ILIMIT)") (class "Default")
      (node (ref "LIM7") (pin "5") (pinfunction "ILIMIT_5") (pintype "passive"))
      (node (ref "POT10") (pin "1") (pinfunction "A_1") (pintype "passive"))
    )
    (net (code "150") (name "Net-(LIM8-ILIMIT)") (class "Default")
      (node (ref "LIM8") (pin "5") (pinfunction "ILIMIT_5") (pintype "passive"))
      (node (ref "POT12") (pin "1") (pinfunction "A_1") (pintype "passive"))
    )
    (net (code "151") (name "Net-(PIC1-RA0)") (class "Default")
      (node (ref "PIC1") (pin "7") (pinfunction "RA0_7") (pintype "passive"))
      (node (ref "R50") (pin "1") (pinfunction "1_1") (pintype "passive"))
    )
    (net (code "152") (name "Net-(PIC2-RA0)") (class "Default")
      (node (ref "PIC2") (pin "7") (pinfunction "RA0_7") (pintype "passive"))
      (node (ref "R51") (pin "1") (pinfunction "1_1") (pintype "passive"))
    )
    (net (code "153") (name "Net-(PIC3-RA0)") (class "Default")
      (node (ref "PIC3") (pin "7") (pinfunction "RA0_7") (pintype "passive"))
      (node (ref "R52") (pin "1") (pinfunction "1_1") (pintype "passive"))
    )
    (net (code "154") (name "Net-(PIC4-RA0)") (class "Default")
      (node (ref "PIC4") (pin "7") (pinfunction "RA0_7") (pintype "passive"))
      (node (ref "R53") (pin "1") (pinfunction "1_1") (pintype "passive"))
    )
    (net (code "155") (name "Net-(POT2-B)") (class "Default")
      (node (ref "POT2") (pin "2") (pinfunction "C_2") (pintype "passive"))
      (node (ref "POT2") (pin "3") (pinfunction "B_3") (pintype "passive"))
      (node (ref "R41") (pin "2") (pinfunction "2_2") (pintype "passive"))
    )
    (net (code "156") (name "Net-(POT5-B)") (class "Default")
      (node (ref "POT5") (pin "2") (pinfunction "C_2") (pintype "passive"))
      (node (ref "POT5") (pin "3") (pinfunction "B_3") (pintype "passive"))
      (node (ref "R42") (pin "2") (pinfunction "2_2") (pintype "passive"))
    )
    (net (code "157") (name "Net-(POT8-B)") (class "Default")
      (node (ref "POT8") (pin "2") (pinfunction "C_2") (pintype "passive"))
      (node (ref "POT8") (pin "3") (pinfunction "B_3") (pintype "passive"))
      (node (ref "R43") (pin "2") (pinfunction "2_2") (pintype "passive"))
    )
    (net (code "158") (name "Net-(POT11-B)") (class "Default")
      (node (ref "POT11") (pin "2") (pinfunction "C_2") (pintype "passive"))
      (node (ref "POT11") (pin "3") (pinfunction "B_3") (pintype "passive"))
      (node (ref "R44") (pin "2") (pinfunction "2_2") (pintype "passive"))
    )
    (net (code "159") (name "Net-(SW1A-R1{slash}C1)") (class "Default")
      (node (ref "R33") (pin "2") (pinfunction "2_2") (pintype "passive"))
      (node (ref "SW1A") (pin "6") (pinfunction "R1/C1_6") (pintype "passive"))
    )
    (net (code "160") (name "Net-(SW1B-R1{slash}C1)") (class "Default")
      (node (ref "R34") (pin "1") (pinfunction "1_1") (pintype "passive"))
      (node (ref "SW1B") (pin "6") (pinfunction "R1/C1_6") (pintype "passive"))
    )
    (net (code "161") (name "Net-(SW2A-R1{slash}C1)") (class "Default")
      (node (ref "R35") (pin "2") (pinfunction "2_2") (pintype "passive"))
      (node (ref "SW2A") (pin "6") (pinfunction "R1/C1_6") (pintype "passive"))
    )
    (net (code "162") (name "Net-(SW2B-R1{slash}C1)") (class "Default")
      (node (ref "R36") (pin "1") (pinfunction "1_1") (pintype "passive"))
      (node (ref "SW2B") (pin "6") (pinfunction "R1/C1_6") (pintype "passive"))
    )
    (net (code "163") (name "Net-(SW3A-R1{slash}C1)") (class "Default")
      (node (ref "R37") (pin "2") (pinfunction "2_2") (pintype "passive"))
      (node (ref "SW3A") (pin "6") (pinfunction "R1/C1_6") (pintype "passive"))
    )
    (net (code "164") (name "Net-(SW3B-R1{slash}C1)") (class "Default")
      (node (ref "R38") (pin "1") (pinfunction "1_1") (pintype "passive"))
      (node (ref "SW3B") (pin "6") (pinfunction "R1/C1_6") (pintype "passive"))
    )
    (net (code "165") (name "Net-(SW4A-R1{slash}C1)") (class "Default")
      (node (ref "R39") (pin "2") (pinfunction "2_2") (pintype "passive"))
      (node (ref "SW4A") (pin "6") (pinfunction "R1/C1_6") (pintype "passive"))
    )
    (net (code "166") (name "Net-(SW4B-R1{slash}C1)") (class "Default")
      (node (ref "R40") (pin "1") (pinfunction "1_1") (pintype "passive"))
      (node (ref "SW4B") (pin "6") (pinfunction "R1/C1_6") (pintype "passive"))
    )
    (net (code "167") (name "unconnected-(DCDC1-NC-Pad9)") (class "Default")
      (node (ref "DCDC1") (pin "9") (pinfunction "NC_9") (pintype "passive"))
    )
    (net (code "168") (name "unconnected-(DCDC1-NC-Pad10)") (class "Default")
      (node (ref "DCDC1") (pin "10") (pinfunction "NC_10") (pintype "passive"))
    )
    (net (code "169") (name "unconnected-(DCDC1-NC-Pad22)") (class "Default")
      (node (ref "DCDC1") (pin "22") (pinfunction "NC_22") (pintype "passive"))
    )
    (net (code "170") (name "unconnected-(DCDC1-PFO-Pad13)") (class "Default")
      (node (ref "DCDC1") (pin "13") (pinfunction "PFO_13") (pintype "passive"))
    )
    (net (code "171") (name "unconnected-(DCDC1-PGOOD-Pad17)") (class "Default")
      (node (ref "DCDC1") (pin "17") (pinfunction "PGOOD_17") (pintype "passive"))
    )
    (net (code "172") (name "unconnected-(DCDC2-NC-Pad9)") (class "Default")
      (node (ref "DCDC2") (pin "9") (pinfunction "NC_9") (pintype "passive"))
    )
    (net (code "173") (name "unconnected-(DCDC2-NC-Pad10)") (class "Default")
      (node (ref "DCDC2") (pin "10") (pinfunction "NC_10") (pintype "passive"))
    )
    (net (code "174") (name "unconnected-(DCDC2-NC-Pad22)") (class "Default")
      (node (ref "DCDC2") (pin "22") (pinfunction "NC_22") (pintype "passive"))
    )
    (net (code "175") (name "unconnected-(DCDC2-PFO-Pad13)") (class "Default")
      (node (ref "DCDC2") (pin "13") (pinfunction "PFO_13") (pintype "passive"))
    )
    (net (code "176") (name "unconnected-(DCDC2-PGOOD-Pad17)") (class "Default")
      (node (ref "DCDC2") (pin "17") (pinfunction "PGOOD_17") (pintype "passive"))
    )
    (net (code "177") (name "unconnected-(DCDC3-NC-Pad9)") (class "Default")
      (node (ref "DCDC3") (pin "9") (pinfunction "NC_9") (pintype "passive"))
    )
    (net (code "178") (name "unconnected-(DCDC3-NC-Pad10)") (class "Default")
      (node (ref "DCDC3") (pin "10") (pinfunction "NC_10") (pintype "passive"))
    )
    (net (code "179") (name "unconnected-(DCDC3-NC-Pad22)") (class "Default")
      (node (ref "DCDC3") (pin "22") (pinfunction "NC_22") (pintype "passive"))
    )
    (net (code "180") (name "unconnected-(DCDC3-PFO-Pad13)") (class "Default")
      (node (ref "DCDC3") (pin "13") (pinfunction "PFO_13") (pintype "passive"))
    )
    (net (code "181") (name "unconnected-(DCDC3-PGOOD-Pad17)") (class "Default")
      (node (ref "DCDC3") (pin "17") (pinfunction "PGOOD_17") (pintype "passive"))
    )
    (net (code "182") (name "unconnected-(DCDC4-NC-Pad9)") (class "Default")
      (node (ref "DCDC4") (pin "9") (pinfunction "NC_9") (pintype "passive"))
    )
    (net (code "183") (name "unconnected-(DCDC4-NC-Pad10)") (class "Default")
      (node (ref "DCDC4") (pin "10") (pinfunction "NC_10") (pintype "passive"))
    )
    (net (code "184") (name "unconnected-(DCDC4-NC-Pad22)") (class "Default")
      (node (ref "DCDC4") (pin "22") (pinfunction "NC_22") (pintype "passive"))
    )
    (net (code "185") (name "unconnected-(DCDC4-PFO-Pad13)") (class "Default")
      (node (ref "DCDC4") (pin "13") (pinfunction "PFO_13") (pintype "passive"))
    )
    (net (code "186") (name "unconnected-(DCDC4-PGOOD-Pad17)") (class "Default")
      (node (ref "DCDC4") (pin "17") (pinfunction "PGOOD_17") (pintype "passive"))
    )
    (net (code "187") (name "unconnected-(PIN2-Pad38)") (class "Default")
      (node (ref "PIN2") (pin "38") (pinfunction "38_38") (pintype "passive"))
    )
    (net (code "188") (name "unconnected-(PIN2-Pad40)") (class "Default")
      (node (ref "PIN2") (pin "40") (pinfunction "40_40") (pintype "passive"))
    )
  )
)
